# S7G7_footprint_simplified_w_ethernet_v1p.net
KiCad netlist of a schematic drawn in EAGLE
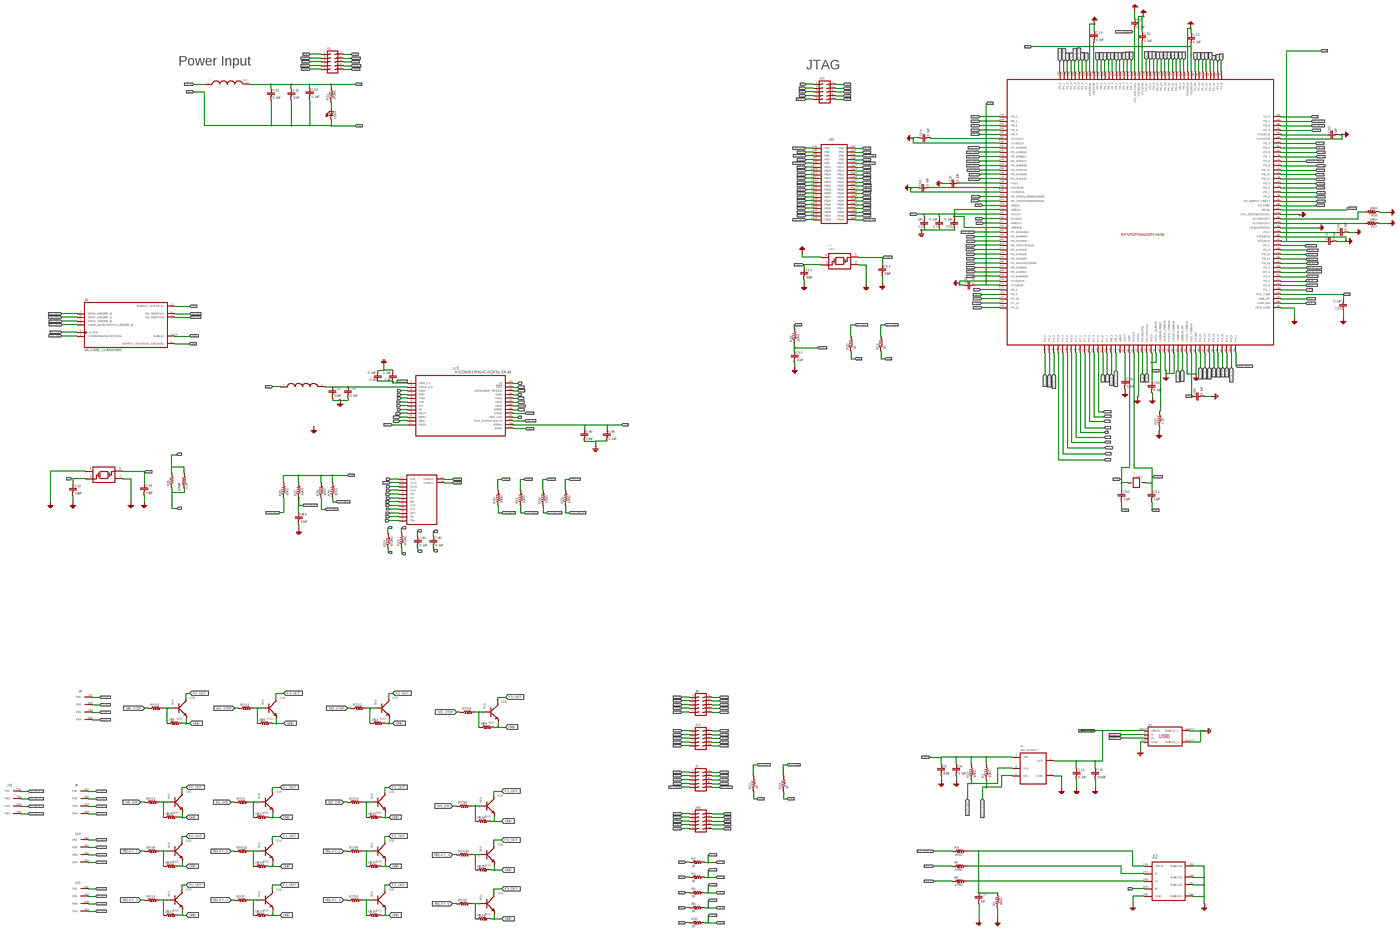
[diagram p0: schematic, sheet 1, overview]
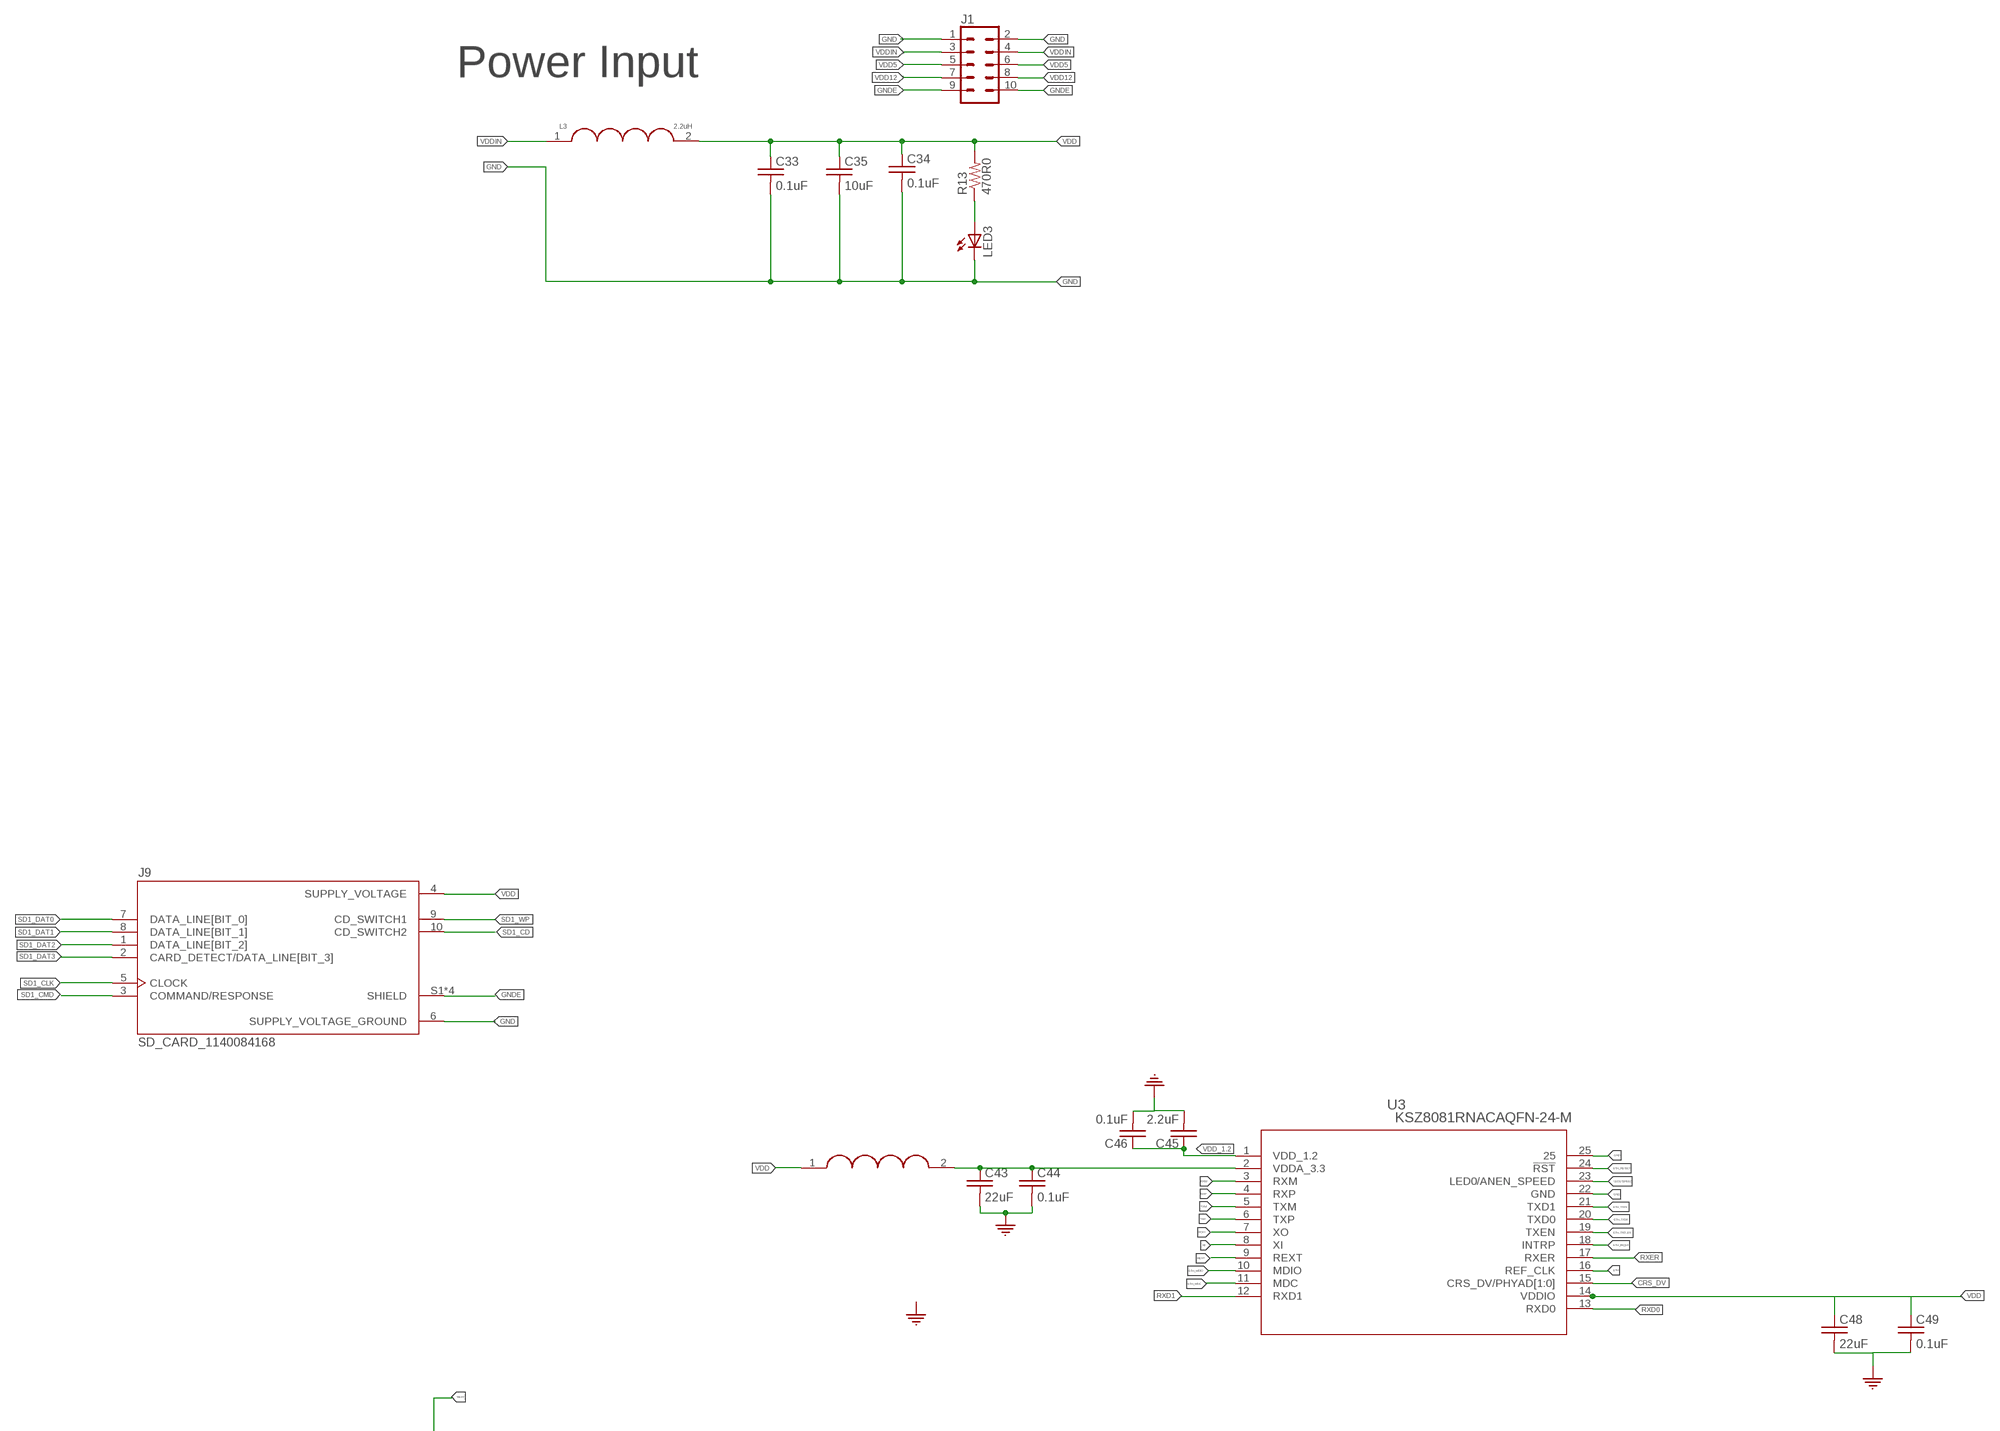
[diagram p1: schematic, sheet 1, part 1 of 4]
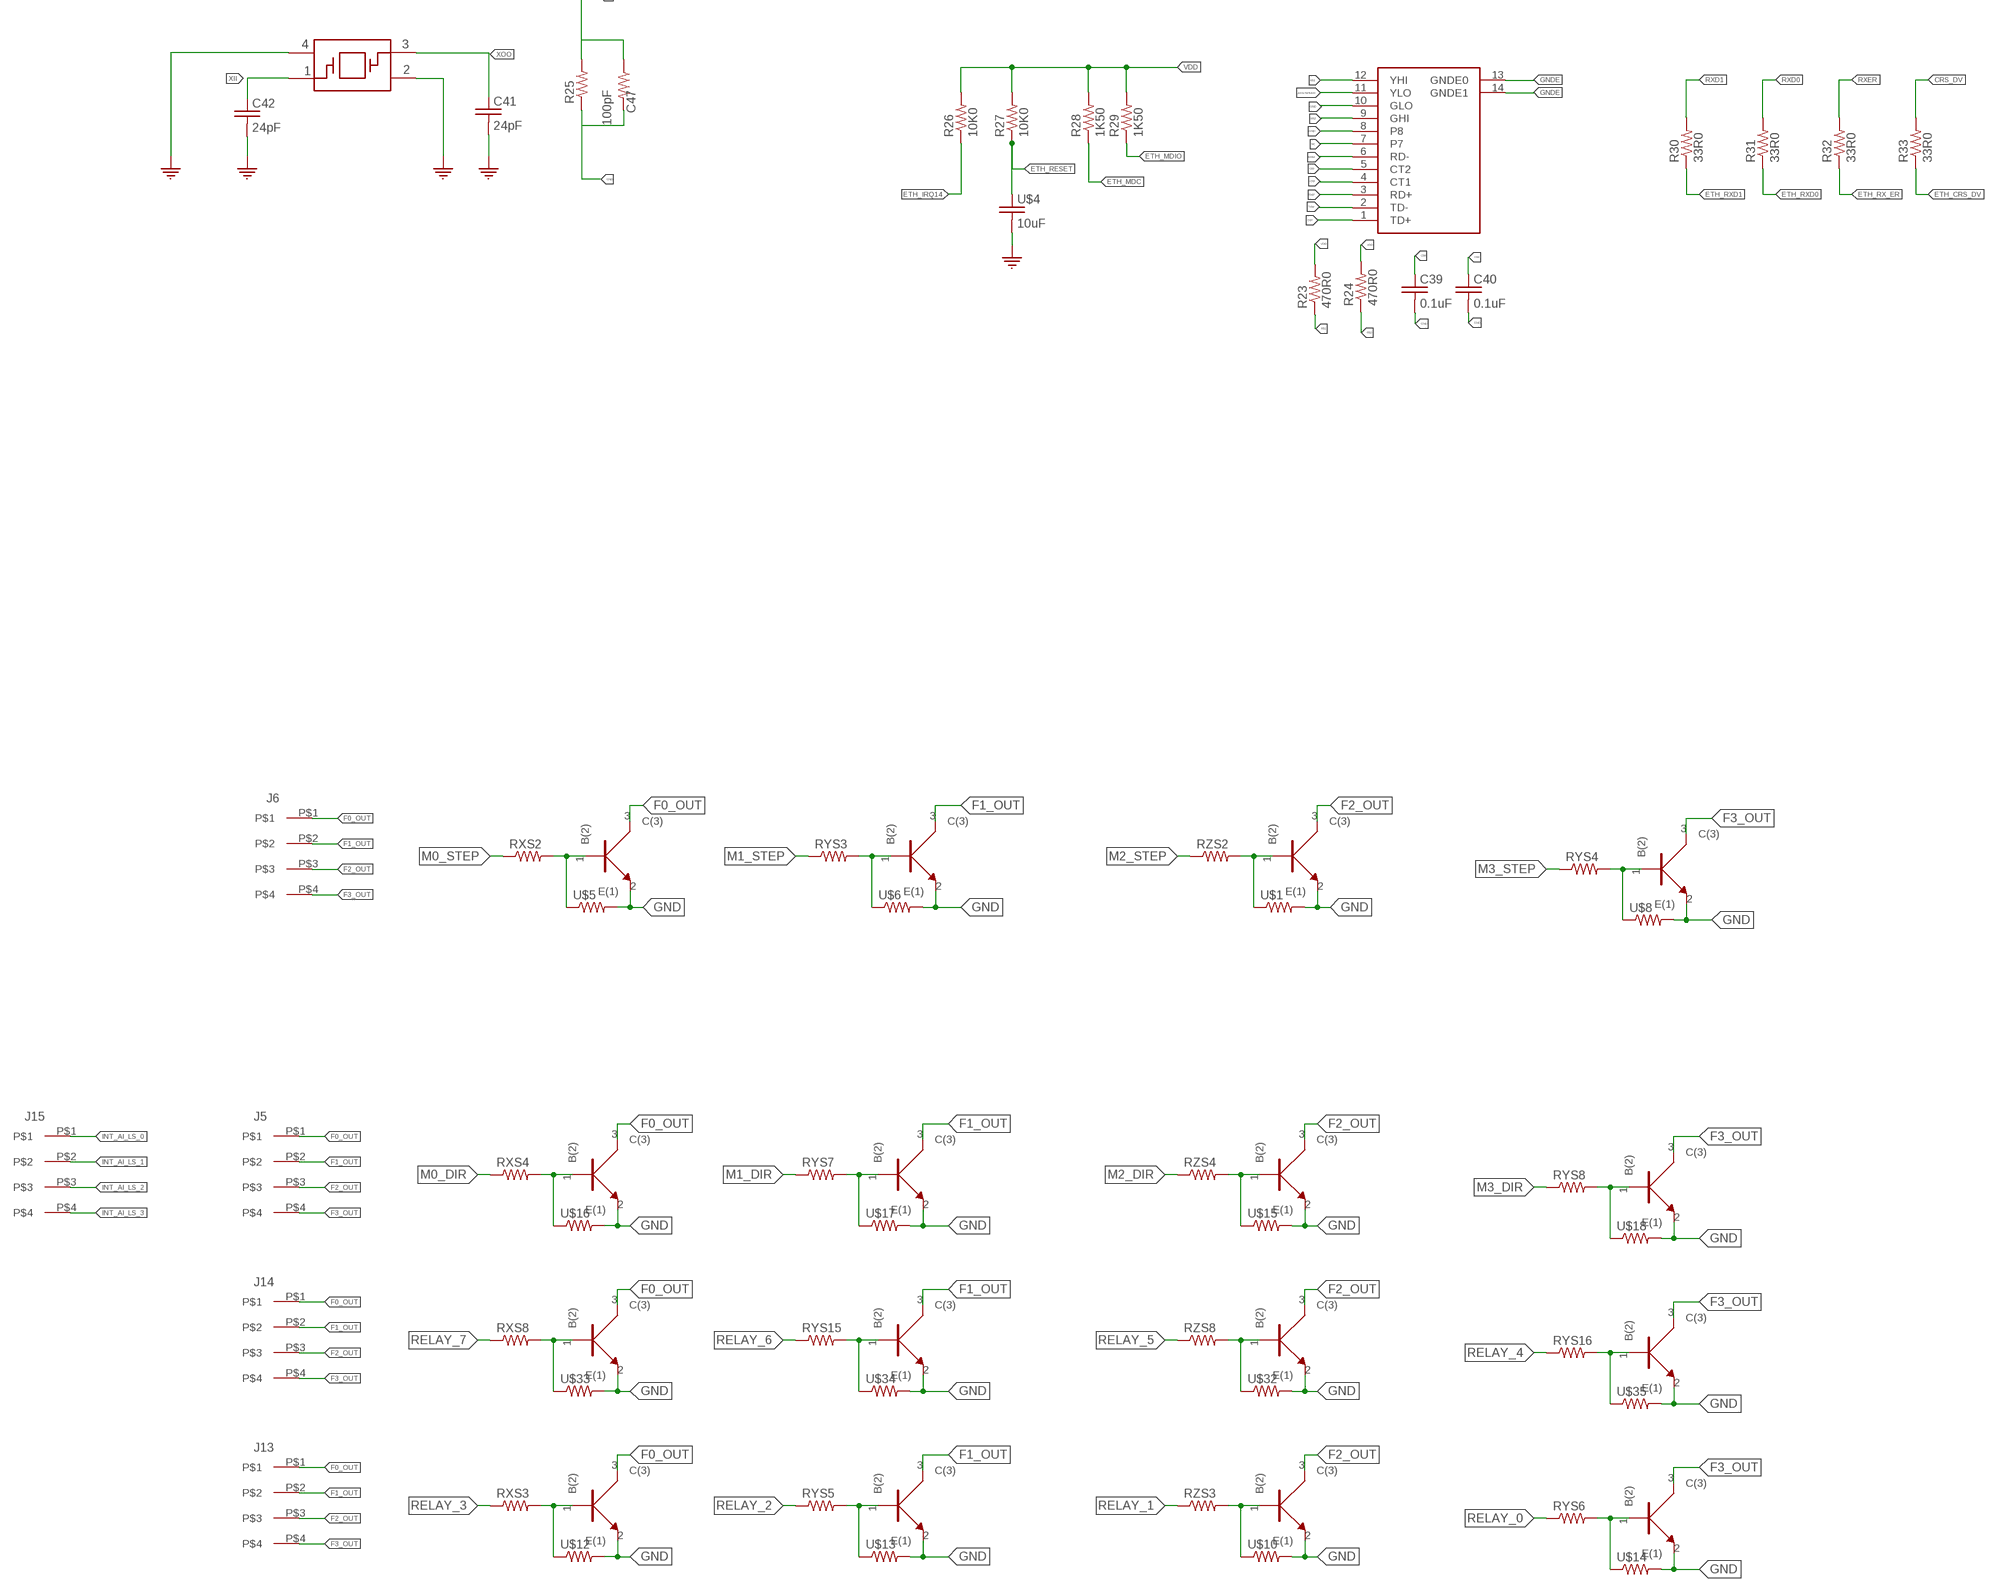
[diagram p2: schematic, sheet 1, part 2 of 4]
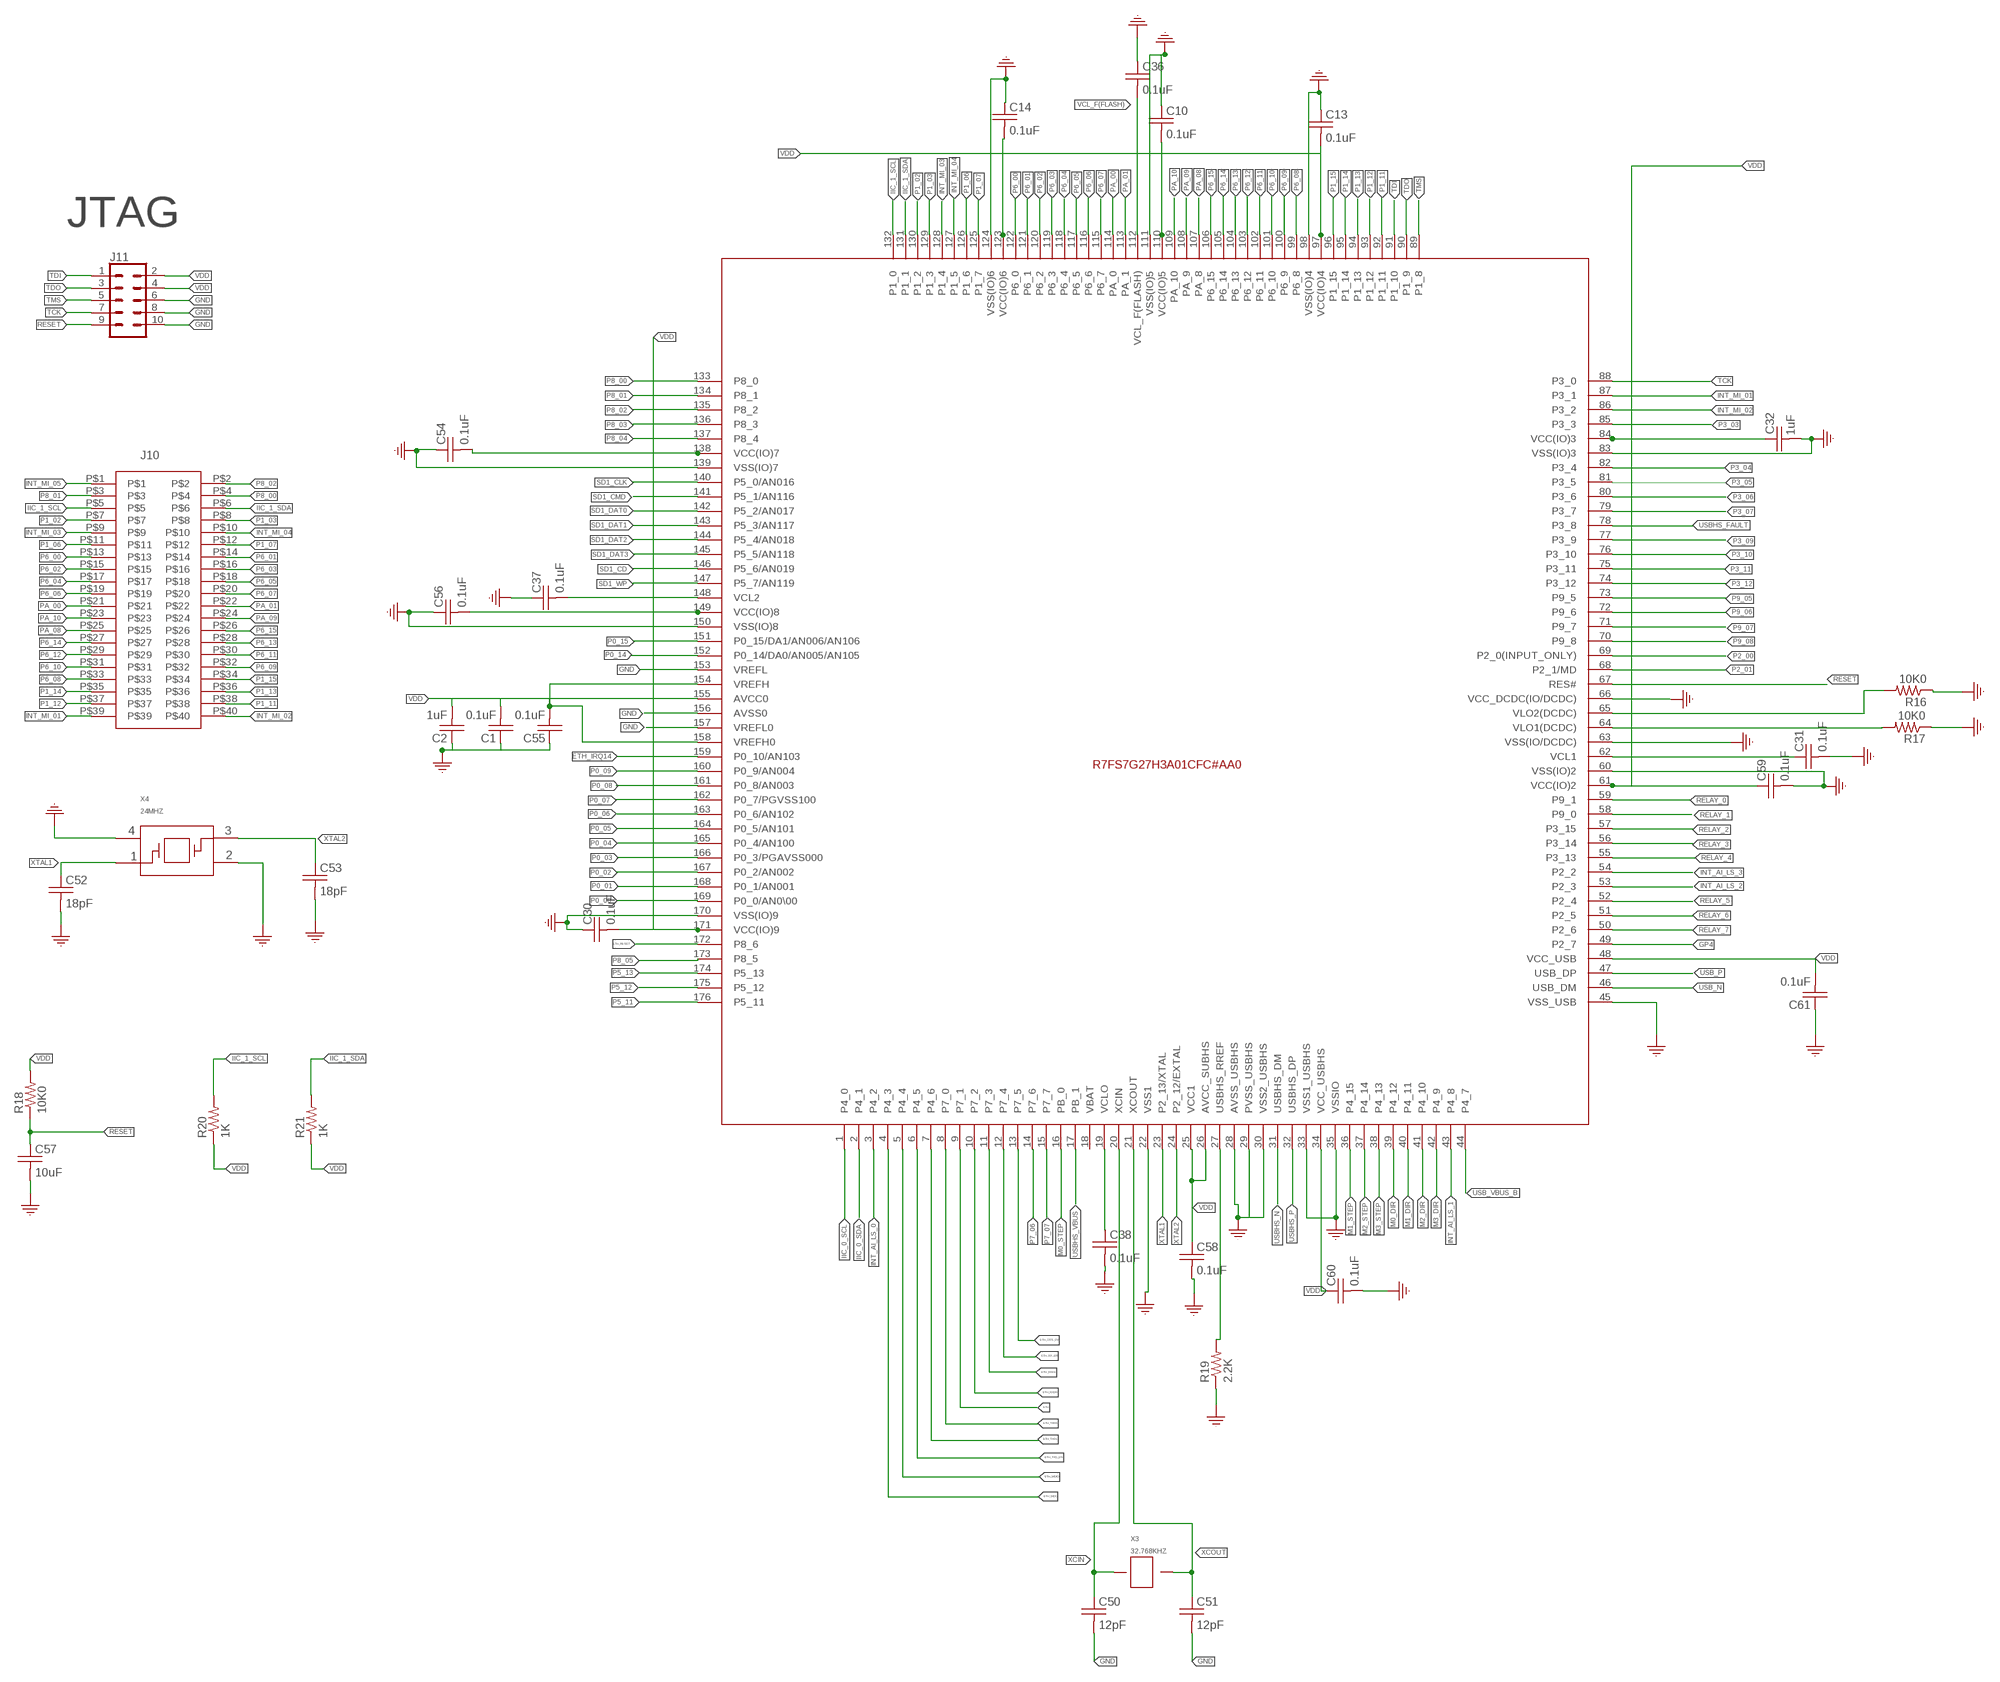
[diagram p3: schematic, sheet 1, part 3 of 4]
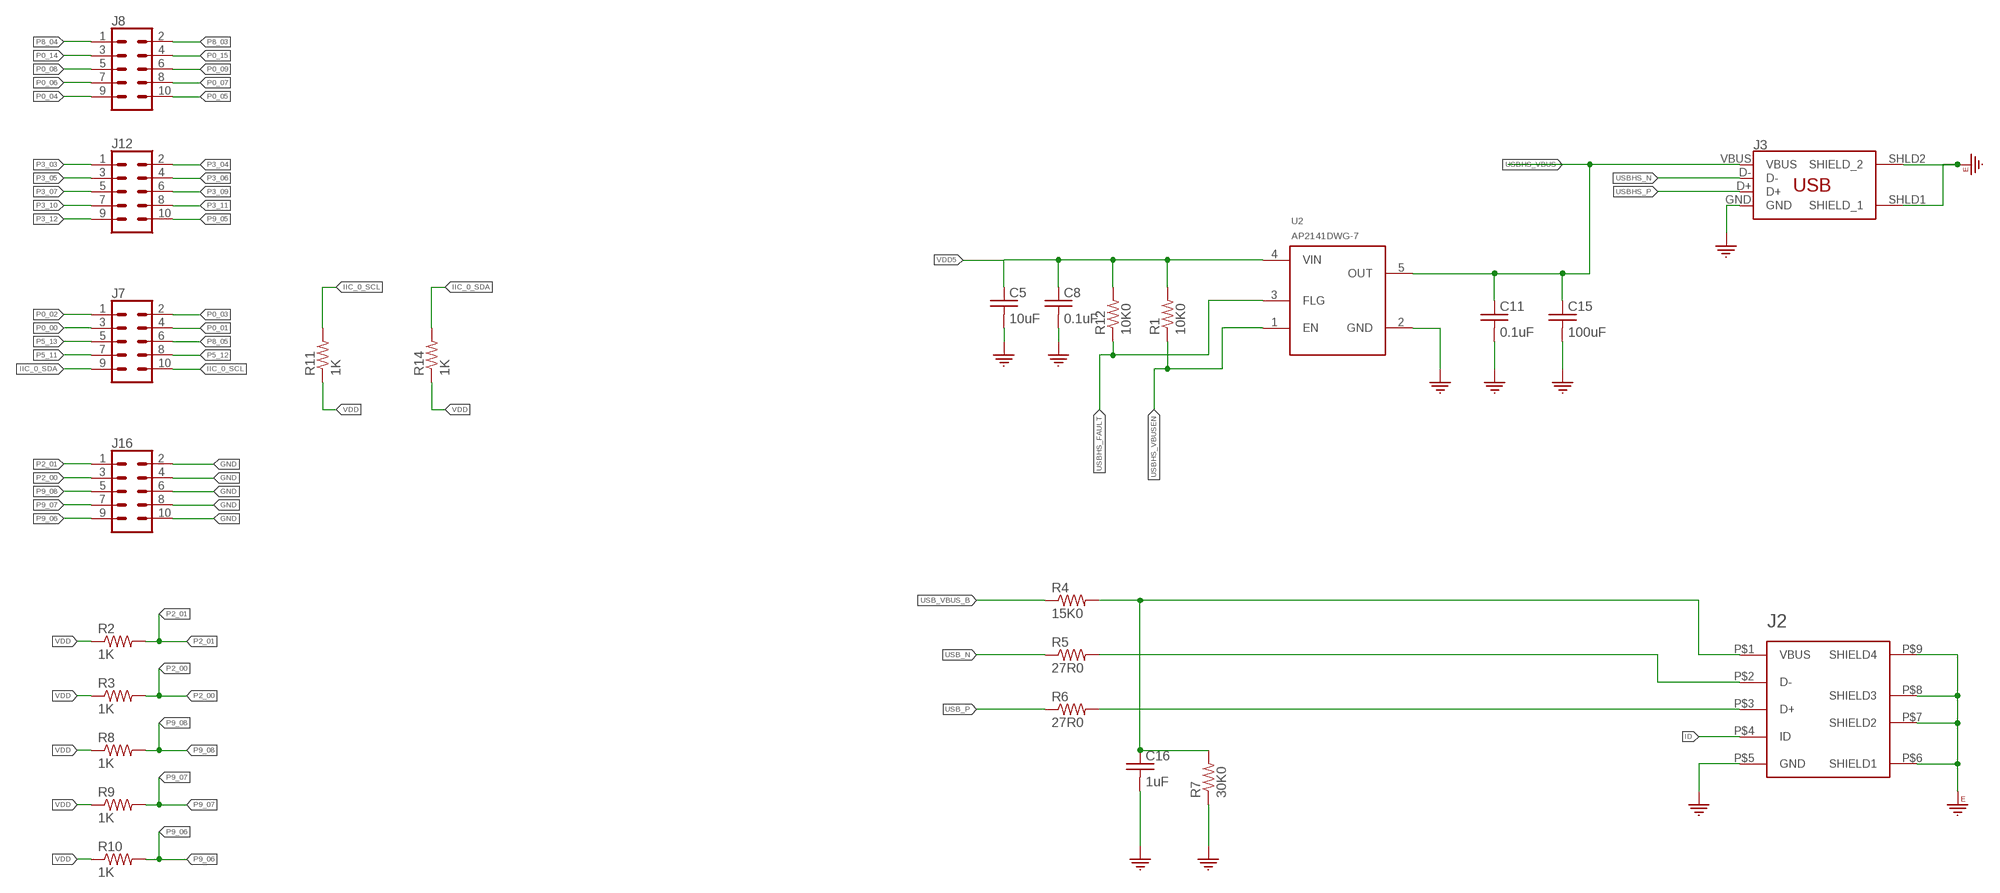
[diagram p4: schematic, sheet 1, part 4 of 4]

(export (version "E")
  (design (tool "Eeschema 10.0.6"))
  (components
    (comp (ref "C1")
      (value "0.1uF")
      (footprint "eagle-import:0402")
      (libsource (lib "eagle-import") (part "C_0402"))
    )
    (comp (ref "C2")
      (value "1uF")
      (footprint "eagle-import:0402")
      (libsource (lib "eagle-import") (part "C_0402"))
    )
    (comp (ref "C5")
      (value "10uF")
      (footprint "eagle-import:0402")
      (libsource (lib "eagle-import") (part "C_0402"))
    )
    (comp (ref "C8")
      (value "0.1uF")
      (footprint "eagle-import:0402")
      (libsource (lib "eagle-import") (part "C_0402"))
    )
    (comp (ref "C10")
      (value "0.1uF")
      (footprint "eagle-import:0402")
      (libsource (lib "eagle-import") (part "C_0402"))
    )
    (comp (ref "C11")
      (value "0.1uF")
      (footprint "eagle-import:0402")
      (libsource (lib "eagle-import") (part "C_0402"))
    )
    (comp (ref "C13")
      (value "0.1uF")
      (footprint "eagle-import:0402")
      (libsource (lib "eagle-import") (part "C_0402"))
    )
    (comp (ref "C14")
      (value "0.1uF")
      (footprint "eagle-import:0402")
      (libsource (lib "eagle-import") (part "C_0402"))
    )
    (comp (ref "C15")
      (value "100uF")
      (footprint "eagle-import:C1210")
      (libsource (lib "eagle-import") (part "C_1210"))
    )
    (comp (ref "C16")
      (value "1uF")
      (footprint "eagle-import:0402")
      (libsource (lib "eagle-import") (part "C_0402"))
    )
    (comp (ref "C30")
      (value "0.1uF")
      (footprint "eagle-import:0402")
      (libsource (lib "eagle-import") (part "C_0402"))
    )
    (comp (ref "C31")
      (value "0.1uF")
      (footprint "eagle-import:0402")
      (libsource (lib "eagle-import") (part "C_0402"))
    )
    (comp (ref "C32")
      (value "1uF")
      (footprint "eagle-import:0402")
      (libsource (lib "eagle-import") (part "C_0402"))
    )
    (comp (ref "C33")
      (value "0.1uF")
      (footprint "eagle-import:0402")
      (libsource (lib "eagle-import") (part "C_0402"))
    )
    (comp (ref "C34")
      (value "0.1uF")
      (footprint "eagle-import:0402")
      (libsource (lib "eagle-import") (part "C_0402"))
    )
    (comp (ref "C35")
      (value "10uF")
      (footprint "eagle-import:0402")
      (libsource (lib "eagle-import") (part "C_0402"))
    )
    (comp (ref "C36")
      (value "0.1uF")
      (footprint "eagle-import:0402")
      (libsource (lib "eagle-import") (part "C_0402"))
    )
    (comp (ref "C37")
      (value "0.1uF")
      (footprint "eagle-import:0402")
      (libsource (lib "eagle-import") (part "C_0402"))
    )
    (comp (ref "C38")
      (value "0.1uF")
      (footprint "eagle-import:0402")
      (libsource (lib "eagle-import") (part "C_0402"))
    )
    (comp (ref "C39")
      (value "0.1uF")
      (footprint "eagle-import:0402")
      (libsource (lib "eagle-import") (part "C_0402"))
    )
    (comp (ref "C40")
      (value "0.1uF")
      (footprint "eagle-import:0402")
      (libsource (lib "eagle-import") (part "C_0402"))
    )
    (comp (ref "C41")
      (value "24pF")
      (footprint "eagle-import:0402")
      (libsource (lib "eagle-import") (part "C_0402"))
    )
    (comp (ref "C42")
      (value "24pF")
      (footprint "eagle-import:0402")
      (libsource (lib "eagle-import") (part "C_0402"))
    )
    (comp (ref "C43")
      (value "22uF")
      (footprint "eagle-import:0603")
      (libsource (lib "eagle-import") (part "C_0603"))
    )
    (comp (ref "C44")
      (value "0.1uF")
      (footprint "eagle-import:0402")
      (libsource (lib "eagle-import") (part "C_0402"))
    )
    (comp (ref "C45")
      (value "2.2uF")
      (footprint "eagle-import:0402")
      (libsource (lib "eagle-import") (part "C_0402"))
    )
    (comp (ref "C46")
      (value "0.1uF")
      (footprint "eagle-import:0402")
      (libsource (lib "eagle-import") (part "C_0402"))
    )
    (comp (ref "C47")
      (value "100pF")
      (footprint "eagle-import:0402")
      (libsource (lib "eagle-import") (part "R_0402"))
    )
    (comp (ref "C48")
      (value "22uF")
      (footprint "eagle-import:0603")
      (libsource (lib "eagle-import") (part "C_0603"))
    )
    (comp (ref "C49")
      (value "0.1uF")
      (footprint "eagle-import:0402")
      (libsource (lib "eagle-import") (part "C_0402"))
    )
    (comp (ref "C50")
      (value "12pF")
      (footprint "eagle-import:0402")
      (libsource (lib "eagle-import") (part "C_0402"))
    )
    (comp (ref "C51")
      (value "12pF")
      (footprint "eagle-import:0402")
      (libsource (lib "eagle-import") (part "C_0402"))
    )
    (comp (ref "C52")
      (value "18pF")
      (footprint "eagle-import:0402")
      (libsource (lib "eagle-import") (part "C_0402"))
    )
    (comp (ref "C53")
      (value "18pF")
      (footprint "eagle-import:0402")
      (libsource (lib "eagle-import") (part "C_0402"))
    )
    (comp (ref "C54")
      (value "0.1uF")
      (footprint "eagle-import:0402")
      (libsource (lib "eagle-import") (part "C_0402"))
    )
    (comp (ref "C55")
      (value "0.1uF")
      (footprint "eagle-import:0402")
      (libsource (lib "eagle-import") (part "C_0402"))
    )
    (comp (ref "C56")
      (value "0.1uF")
      (footprint "eagle-import:0402")
      (libsource (lib "eagle-import") (part "C_0402"))
    )
    (comp (ref "C57")
      (value "10uF")
      (footprint "eagle-import:0402")
      (libsource (lib "eagle-import") (part "C_0402"))
    )
    (comp (ref "C58")
      (value "0.1uF")
      (footprint "eagle-import:0402")
      (libsource (lib "eagle-import") (part "C_0402"))
    )
    (comp (ref "C59")
      (value "0.1uF")
      (footprint "eagle-import:0402")
      (libsource (lib "eagle-import") (part "C_0402"))
    )
    (comp (ref "C60")
      (value "0.1uF")
      (footprint "eagle-import:0402")
      (libsource (lib "eagle-import") (part "C_0402"))
    )
    (comp (ref "C61")
      (value "0.1uF")
      (footprint "eagle-import:0402")
      (libsource (lib "eagle-import") (part "C_0402"))
    )
    (comp (ref "FB2/2")
      (value "FB_0805_120_OHM")
      (footprint "eagle-import:0805")
      (libsource (lib "eagle-import") (part "FB_0805_120_OHM"))
    )
    (comp (ref "J1")
      (value "CONN_05X2PTH")
      (footprint "eagle-import:2X5")
      (libsource (lib "eagle-import") (part "CONN_05X2PTH"))
    )
    (comp (ref "J2")
      (value "USB_MICRO-B")
      (footprint "eagle-import:USB_MICRO-B")
      (libsource (lib "eagle-import") (part "USB_MICRO-B"))
    )
    (comp (ref "J3")
      (value "USB_A")
      (footprint "eagle-import:USB_A_SMT")
      (libsource (lib "eagle-import") (part "USB_A"))
    )
    (comp (ref "J4")
      (value "RJ45_WITH_ELEC")
      (footprint "eagle-import:RJ45_TH_ELEC")
      (libsource (lib "eagle-import") (part "RJ45_WITH_ELEC"))
    )
    (comp (ref "J5")
      (value "3.81MM_1_X_4_RT_ANGLE_PLUG_HEADER")
      (footprint "eagle-import:1X4_3.81MM_PITCH")
      (libsource (lib "eagle-import") (part "3.81MM_1_X_4_RT_ANGLE_PLUG_HEADER"))
    )
    (comp (ref "J6")
      (value "3.81MM_1_X_4_RT_ANGLE_PLUG_HEADER")
      (footprint "eagle-import:1X4_3.81MM_PITCH")
      (libsource (lib "eagle-import") (part "3.81MM_1_X_4_RT_ANGLE_PLUG_HEADER"))
    )
    (comp (ref "J7")
      (value "CONN_05X2NO_SILK")
      (footprint "eagle-import:2X5_NOSILK")
      (libsource (lib "eagle-import") (part "CONN_05X2NO_SILK"))
    )
    (comp (ref "J8")
      (value "CONN_05X2NO_SILK")
      (footprint "eagle-import:2X5_NOSILK")
      (libsource (lib "eagle-import") (part "CONN_05X2NO_SILK"))
    )
    (comp (ref "J9")
      (value "SD_CARD_1140084168")
      (footprint "eagle-import:AMPHENOL_1140084168")
      (fields
        (field (name "DIGI-KEY_PART_NUMBER") "114-00841-68-1-ND")
        (field (name "MF") "Amphenol ICC")
        (field (name "MP") "114-00841-68")
      )
      (libsource (lib "eagle-import") (part "SD_CARD_1140084168"))
    )
    (comp (ref "J10")
      (value "HEADER_2_X_20_GENERIC")
      (footprint "eagle-import:HEADER_2_X_20_.1_INCH")
      (libsource (lib "eagle-import") (part "HEADER_2_X_20_GENERIC"))
    )
    (comp (ref "J11")
      (value "CONN_05X2PTH")
      (footprint "eagle-import:2X5")
      (libsource (lib "eagle-import") (part "CONN_05X2PTH"))
    )
    (comp (ref "J12")
      (value "CONN_05X2NO_SILK")
      (footprint "eagle-import:2X5_NOSILK")
      (libsource (lib "eagle-import") (part "CONN_05X2NO_SILK"))
    )
    (comp (ref "J13")
      (value "3.81MM_1_X_4_RT_ANGLE_PLUG_HEADER")
      (footprint "eagle-import:1X4_3.81MM_PITCH")
      (libsource (lib "eagle-import") (part "3.81MM_1_X_4_RT_ANGLE_PLUG_HEADER"))
    )
    (comp (ref "J14")
      (value "3.81MM_1_X_4_RT_ANGLE_PLUG_HEADER")
      (footprint "eagle-import:1X4_3.81MM_PITCH")
      (libsource (lib "eagle-import") (part "3.81MM_1_X_4_RT_ANGLE_PLUG_HEADER"))
    )
    (comp (ref "J15")
      (value "3.81MM_1_X_4_RT_ANGLE_PLUG_HEADER")
      (footprint "eagle-import:1X4_3.81MM_PITCH")
      (libsource (lib "eagle-import") (part "3.81MM_1_X_4_RT_ANGLE_PLUG_HEADER"))
    )
    (comp (ref "J16")
      (value "CONN_05X2SHD_SMD")
      (footprint "eagle-import:2X5-SHROUDED_SMD")
      (libsource (lib "eagle-import") (part "CONN_05X2SHD_SMD"))
    )
    (comp (ref "L3")
      (value "2.2uH")
      (footprint "eagle-import:1008_(2520_METRIC)")
      (libsource (lib "eagle-import") (part "INDUCTOR_1008_2.2_MH_1.3A"))
    )
    (comp (ref "LED3")
      (value "LED_0805_GREEN")
      (footprint "eagle-import:LED_0805_GREEN")
      (libsource (lib "eagle-import") (part "LED_0805_GREEN"))
    )
    (comp (ref "R1")
      (value "10K0")
      (footprint "eagle-import:0402")
      (libsource (lib "eagle-import") (part "R_0402"))
    )
    (comp (ref "R2")
      (value "1K")
      (footprint "eagle-import:0402")
      (libsource (lib "eagle-import") (part "R_0402"))
    )
    (comp (ref "R3")
      (value "1K")
      (footprint "eagle-import:0402")
      (libsource (lib "eagle-import") (part "R_0402"))
    )
    (comp (ref "R4")
      (value "15K0")
      (footprint "eagle-import:0402")
      (libsource (lib "eagle-import") (part "R_0402"))
    )
    (comp (ref "R5")
      (value "27R0")
      (footprint "eagle-import:0402")
      (libsource (lib "eagle-import") (part "R_0402"))
    )
    (comp (ref "R6")
      (value "27R0")
      (footprint "eagle-import:0402")
      (libsource (lib "eagle-import") (part "R_0402"))
    )
    (comp (ref "R7")
      (value "30K0")
      (footprint "eagle-import:0402")
      (libsource (lib "eagle-import") (part "R_0402"))
    )
    (comp (ref "R8")
      (value "1K")
      (footprint "eagle-import:0402")
      (libsource (lib "eagle-import") (part "R_0402"))
    )
    (comp (ref "R9")
      (value "1K")
      (footprint "eagle-import:0402")
      (libsource (lib "eagle-import") (part "R_0402"))
    )
    (comp (ref "R10")
      (value "1K")
      (footprint "eagle-import:0402")
      (libsource (lib "eagle-import") (part "R_0402"))
    )
    (comp (ref "R11")
      (value "1K")
      (footprint "eagle-import:0402")
      (libsource (lib "eagle-import") (part "R_0402"))
    )
    (comp (ref "R12")
      (value "10K0")
      (footprint "eagle-import:0402")
      (libsource (lib "eagle-import") (part "R_0402"))
    )
    (comp (ref "R13")
      (value "470R0")
      (footprint "eagle-import:0402")
      (libsource (lib "eagle-import") (part "R_0402"))
    )
    (comp (ref "R14")
      (value "1K")
      (footprint "eagle-import:0402")
      (libsource (lib "eagle-import") (part "R_0402"))
    )
    (comp (ref "R16")
      (value "10K0")
      (footprint "eagle-import:0402")
      (libsource (lib "eagle-import") (part "R_0402"))
    )
    (comp (ref "R17")
      (value "10K0")
      (footprint "eagle-import:0402")
      (libsource (lib "eagle-import") (part "R_0402"))
    )
    (comp (ref "R18")
      (value "10K0")
      (footprint "eagle-import:0402")
      (libsource (lib "eagle-import") (part "R_0402"))
    )
    (comp (ref "R19")
      (value "2.2K")
      (footprint "eagle-import:0402")
      (libsource (lib "eagle-import") (part "R_0402"))
    )
    (comp (ref "R20")
      (value "1K")
      (footprint "eagle-import:0402")
      (libsource (lib "eagle-import") (part "R_0402"))
    )
    (comp (ref "R21")
      (value "1K")
      (footprint "eagle-import:0402")
      (libsource (lib "eagle-import") (part "R_0402"))
    )
    (comp (ref "R23")
      (value "470R0")
      (footprint "eagle-import:0402")
      (libsource (lib "eagle-import") (part "R_0402"))
    )
    (comp (ref "R24")
      (value "470R0")
      (footprint "eagle-import:0402")
      (libsource (lib "eagle-import") (part "R_0402"))
    )
    (comp (ref "R25")
      (value "6k49")
      (footprint "eagle-import:0402")
      (libsource (lib "eagle-import") (part "R_0402"))
    )
    (comp (ref "R26")
      (value "10K0")
      (footprint "eagle-import:0402")
      (libsource (lib "eagle-import") (part "R_0402"))
    )
    (comp (ref "R27")
      (value "10K0")
      (footprint "eagle-import:0402")
      (libsource (lib "eagle-import") (part "R_0402"))
    )
    (comp (ref "R28")
      (value "1K50")
      (footprint "eagle-import:0402")
      (libsource (lib "eagle-import") (part "R_0402"))
    )
    (comp (ref "R29")
      (value "1K50")
      (footprint "eagle-import:0402")
      (libsource (lib "eagle-import") (part "R_0402"))
    )
    (comp (ref "R30")
      (value "33R0")
      (footprint "eagle-import:0402")
      (libsource (lib "eagle-import") (part "R_0402"))
    )
    (comp (ref "R31")
      (value "33R0")
      (footprint "eagle-import:0402")
      (libsource (lib "eagle-import") (part "R_0402"))
    )
    (comp (ref "R32")
      (value "33R0")
      (footprint "eagle-import:0402")
      (libsource (lib "eagle-import") (part "R_0402"))
    )
    (comp (ref "R33")
      (value "33R0")
      (footprint "eagle-import:0402")
      (libsource (lib "eagle-import") (part "R_0402"))
    )
    (comp (ref "RXS2")
      (value "1K")
      (footprint "eagle-import:0402")
      (libsource (lib "eagle-import") (part "R_0402"))
    )
    (comp (ref "RXS3")
      (value "1K")
      (footprint "eagle-import:0402")
      (libsource (lib "eagle-import") (part "R_0402"))
    )
    (comp (ref "RXS4")
      (value "1K")
      (footprint "eagle-import:0402")
      (libsource (lib "eagle-import") (part "R_0402"))
    )
    (comp (ref "RXS8")
      (value "1K")
      (footprint "eagle-import:0402")
      (libsource (lib "eagle-import") (part "R_0402"))
    )
    (comp (ref "RYS3")
      (value "1K")
      (footprint "eagle-import:0402")
      (libsource (lib "eagle-import") (part "R_0402"))
    )
    (comp (ref "RYS4")
      (value "1K")
      (footprint "eagle-import:0402")
      (libsource (lib "eagle-import") (part "R_0402"))
    )
    (comp (ref "RYS5")
      (value "1K")
      (footprint "eagle-import:0402")
      (libsource (lib "eagle-import") (part "R_0402"))
    )
    (comp (ref "RYS6")
      (value "1K")
      (footprint "eagle-import:0402")
      (libsource (lib "eagle-import") (part "R_0402"))
    )
    (comp (ref "RYS7")
      (value "1K")
      (footprint "eagle-import:0402")
      (libsource (lib "eagle-import") (part "R_0402"))
    )
    (comp (ref "RYS8")
      (value "1K")
      (footprint "eagle-import:0402")
      (libsource (lib "eagle-import") (part "R_0402"))
    )
    (comp (ref "RYS15")
      (value "1K")
      (footprint "eagle-import:0402")
      (libsource (lib "eagle-import") (part "R_0402"))
    )
    (comp (ref "RYS16")
      (value "1K")
      (footprint "eagle-import:0402")
      (libsource (lib "eagle-import") (part "R_0402"))
    )
    (comp (ref "RZS2")
      (value "1K")
      (footprint "eagle-import:0402")
      (libsource (lib "eagle-import") (part "R_0402"))
    )
    (comp (ref "RZS3")
      (value "1K")
      (footprint "eagle-import:0402")
      (libsource (lib "eagle-import") (part "R_0402"))
    )
    (comp (ref "RZS4")
      (value "1K")
      (footprint "eagle-import:0402")
      (libsource (lib "eagle-import") (part "R_0402"))
    )
    (comp (ref "RZS8")
      (value "1K")
      (footprint "eagle-import:0402")
      (libsource (lib "eagle-import") (part "R_0402"))
    )
    (comp (ref "U$1")
      (value "1K")
      (footprint "eagle-import:0402")
      (libsource (lib "eagle-import") (part "R_0402"))
    )
    (comp (ref "U$3")
      (value "XTAL_25_MHZ")
      (footprint "eagle-import:SMD_3225")
      (libsource (lib "eagle-import") (part "XTAL_25_MHZ"))
    )
    (comp (ref "U$4")
      (value "10uF")
      (footprint "eagle-import:0402")
      (libsource (lib "eagle-import") (part "C_0402"))
    )
    (comp (ref "U$5")
      (value "1K")
      (footprint "eagle-import:0402")
      (libsource (lib "eagle-import") (part "R_0402"))
    )
    (comp (ref "U$6")
      (value "1K")
      (footprint "eagle-import:0402")
      (libsource (lib "eagle-import") (part "R_0402"))
    )
    (comp (ref "U$8")
      (value "1K")
      (footprint "eagle-import:0402")
      (libsource (lib "eagle-import") (part "R_0402"))
    )
    (comp (ref "U$10")
      (value "1K")
      (footprint "eagle-import:0402")
      (libsource (lib "eagle-import") (part "R_0402"))
    )
    (comp (ref "U$12")
      (value "1K")
      (footprint "eagle-import:0402")
      (libsource (lib "eagle-import") (part "R_0402"))
    )
    (comp (ref "U$13")
      (value "1K")
      (footprint "eagle-import:0402")
      (libsource (lib "eagle-import") (part "R_0402"))
    )
    (comp (ref "U$14")
      (value "1K")
      (footprint "eagle-import:0402")
      (libsource (lib "eagle-import") (part "R_0402"))
    )
    (comp (ref "U$15")
      (value "1K")
      (footprint "eagle-import:0402")
      (libsource (lib "eagle-import") (part "R_0402"))
    )
    (comp (ref "U$16")
      (value "1K")
      (footprint "eagle-import:0402")
      (libsource (lib "eagle-import") (part "R_0402"))
    )
    (comp (ref "U$17")
      (value "1K")
      (footprint "eagle-import:0402")
      (libsource (lib "eagle-import") (part "R_0402"))
    )
    (comp (ref "U$18")
      (value "1K")
      (footprint "eagle-import:0402")
      (libsource (lib "eagle-import") (part "R_0402"))
    )
    (comp (ref "U$32")
      (value "1K")
      (footprint "eagle-import:0402")
      (libsource (lib "eagle-import") (part "R_0402"))
    )
    (comp (ref "U$33")
      (value "1K")
      (footprint "eagle-import:0402")
      (libsource (lib "eagle-import") (part "R_0402"))
    )
    (comp (ref "U$34")
      (value "1K")
      (footprint "eagle-import:0402")
      (libsource (lib "eagle-import") (part "R_0402"))
    )
    (comp (ref "U$35")
      (value "1K")
      (footprint "eagle-import:0402")
      (libsource (lib "eagle-import") (part "R_0402"))
    )
    (comp (ref "U2")
      (value "AP2141DWG-5")
      (footprint "eagle-import:SOT-23-5")
      (libsource (lib "eagle-import") (part "AP2141DWG-5"))
    )
    (comp (ref "U3")
      (value "KSZ8081RNACAQFN-24-M")
      (footprint "eagle-import:QFN-24-M")
      (fields (field (name "MANUFACTURER_PART_NUMBER") "KSZ8081RNACA"))
      (libsource (lib "eagle-import") (part "KSZ8081RNACAQFN-24-M"))
    )
    (comp (ref "U4")
      (value "S7G2LQFP176")
      (footprint "eagle-import:LQFP176_24X24")
      (fields (field (name "PARTNO") "R7FS7G27H3A01CFC#AA0"))
      (libsource (lib "eagle-import") (part "RENESAS_S7G2_X_176"))
    )
    (comp (ref "U7")
      (value "BC846BW")
      (footprint "eagle-import:SOT323")
      (libsource (lib "eagle-import") (part "BC846BW"))
    )
    (comp (ref "U8")
      (value "BC846BW")
      (footprint "eagle-import:SOT323")
      (libsource (lib "eagle-import") (part "BC846BW"))
    )
    (comp (ref "U9")
      (value "BC846BW")
      (footprint "eagle-import:SOT323")
      (libsource (lib "eagle-import") (part "BC846BW"))
    )
    (comp (ref "U10")
      (value "BC846BW")
      (footprint "eagle-import:SOT323")
      (libsource (lib "eagle-import") (part "BC846BW"))
    )
    (comp (ref "U12")
      (value "BC846BW")
      (footprint "eagle-import:SOT323")
      (libsource (lib "eagle-import") (part "BC846BW"))
    )
    (comp (ref "U13")
      (value "BC846BW")
      (footprint "eagle-import:SOT323")
      (libsource (lib "eagle-import") (part "BC846BW"))
    )
    (comp (ref "U14")
      (value "BC846BW")
      (footprint "eagle-import:SOT323")
      (libsource (lib "eagle-import") (part "BC846BW"))
    )
    (comp (ref "U15")
      (value "BC846BW")
      (footprint "eagle-import:SOT323")
      (libsource (lib "eagle-import") (part "BC846BW"))
    )
    (comp (ref "U16")
      (value "BC846BW")
      (footprint "eagle-import:SOT323")
      (libsource (lib "eagle-import") (part "BC846BW"))
    )
    (comp (ref "U17")
      (value "BC846BW")
      (footprint "eagle-import:SOT323")
      (libsource (lib "eagle-import") (part "BC846BW"))
    )
    (comp (ref "U18")
      (value "BC846BW")
      (footprint "eagle-import:SOT323")
      (libsource (lib "eagle-import") (part "BC846BW"))
    )
    (comp (ref "U19")
      (value "BC846BW")
      (footprint "eagle-import:SOT323")
      (libsource (lib "eagle-import") (part "BC846BW"))
    )
    (comp (ref "U32")
      (value "BC846BW")
      (footprint "eagle-import:SOT323")
      (libsource (lib "eagle-import") (part "BC846BW"))
    )
    (comp (ref "U33")
      (value "BC846BW")
      (footprint "eagle-import:SOT323")
      (libsource (lib "eagle-import") (part "BC846BW"))
    )
    (comp (ref "U34")
      (value "BC846BW")
      (footprint "eagle-import:SOT323")
      (libsource (lib "eagle-import") (part "BC846BW"))
    )
    (comp (ref "U35")
      (value "BC846BW")
      (footprint "eagle-import:SOT323")
      (libsource (lib "eagle-import") (part "BC846BW"))
    )
    (comp (ref "X3")
      (value "32.768KHZ")
      (footprint "eagle-import:SMD_X_2_PADS")
      (libsource (lib "eagle-import") (part "XTAL_32.768KHZ"))
    )
    (comp (ref "X4")
      (value "24MHZ")
      (footprint "eagle-import:SMD_3225")
      (libsource (lib "eagle-import") (part "XTAL_24_MHZ"))
    )
  )
  (nets
    (net (code "1") (name "C58") (class "Default")
      (node (ref "C39") (pin "P$1") (pinfunction "1_P$1") (pintype "passive"))
      (node (ref "J4") (pin "4") (pinfunction "CT1_4") (pintype "bidirectional"))
    )
    (net (code "2") (name "C60") (class "Default")
      (node (ref "C40") (pin "P$1") (pinfunction "1_P$1") (pintype "passive"))
      (node (ref "J4") (pin "5") (pinfunction "CT2_5") (pintype "bidirectional"))
    )
    (net (code "3") (name "CRS_DV") (class "Default")
      (node (ref "R33") (pin "P$2") (pinfunction "2_P$2") (pintype "passive"))
      (node (ref "U3") (pin "15") (pinfunction "CRS_DV/PHYAD[1:0]_15") (pintype "bidirectional"))
    )
    (net (code "4") (name "ETH") (class "Default")
      (node (ref "U3") (pin "16") (pinfunction "REF_CLK_16") (pintype "bidirectional"))
      (node (ref "U4") (pin "9") (pinfunction "P7_1_9") (pintype "bidirectional"))
    )
    (net (code "5") (name "ETH_CRS_DV") (class "Default")
      (node (ref "R33") (pin "P$1") (pinfunction "1_P$1") (pintype "passive"))
      (node (ref "U4") (pin "13") (pinfunction "P7_5_13") (pintype "bidirectional"))
    )
    (net (code "6") (name "ETH_IRQ14") (class "Default")
      (node (ref "R26") (pin "P$1") (pinfunction "1_P$1") (pintype "passive"))
      (node (ref "U3") (pin "18") (pinfunction "INTRP_18") (pintype "bidirectional"))
      (node (ref "U4") (pin "159") (pinfunction "P0_10/AN103_159") (pintype "bidirectional"))
    )
    (net (code "7") (name "ETH_MDC") (class "Default")
      (node (ref "R28") (pin "P$1") (pinfunction "1_P$1") (pintype "passive"))
      (node (ref "U3") (pin "11") (pinfunction "MDC_11") (pintype "input"))
      (node (ref "U4") (pin "4") (pinfunction "P4_3_4") (pintype "bidirectional"))
    )
    (net (code "8") (name "ETH_MDIO") (class "Default")
      (node (ref "R29") (pin "P$1") (pinfunction "1_P$1") (pintype "passive"))
      (node (ref "U3") (pin "10") (pinfunction "MDIO_10") (pintype "bidirectional"))
      (node (ref "U4") (pin "5") (pinfunction "P4_4_5") (pintype "bidirectional"))
    )
    (net (code "9") (name "ETH_RESET") (class "Default")
      (node (ref "R27") (pin "P$1") (pinfunction "1_P$1") (pintype "passive"))
      (node (ref "U$4") (pin "P$1") (pinfunction "1_P$1") (pintype "passive"))
      (node (ref "U3") (pin "24") (pinfunction "~{RST}_24") (pintype "input"))
      (node (ref "U4") (pin "172") (pinfunction "P8_6_172") (pintype "bidirectional"))
    )
    (net (code "10") (name "ETH_RXD0") (class "Default")
      (node (ref "R31") (pin "P$1") (pinfunction "1_P$1") (pintype "passive"))
      (node (ref "U4") (pin "10") (pinfunction "P7_2_10") (pintype "bidirectional"))
    )
    (net (code "11") (name "ETH_RXD1") (class "Default")
      (node (ref "R30") (pin "P$1") (pinfunction "1_P$1") (pintype "passive"))
      (node (ref "U4") (pin "11") (pinfunction "P7_3_11") (pintype "bidirectional"))
    )
    (net (code "12") (name "ETH_RX_ER") (class "Default")
      (node (ref "R32") (pin "P$1") (pinfunction "1_P$1") (pintype "passive"))
      (node (ref "U4") (pin "12") (pinfunction "P7_4_12") (pintype "bidirectional"))
    )
    (net (code "13") (name "ETH_TXD0") (class "Default")
      (node (ref "U3") (pin "20") (pinfunction "TXD0_20") (pintype "input"))
      (node (ref "U4") (pin "8") (pinfunction "P7_0_8") (pintype "bidirectional"))
    )
    (net (code "14") (name "ETH_TXD1") (class "Default")
      (node (ref "U3") (pin "21") (pinfunction "TXD1_21") (pintype "bidirectional"))
      (node (ref "U4") (pin "7") (pinfunction "P4_6_7") (pintype "bidirectional"))
    )
    (net (code "15") (name "ETH_TXD_EN") (class "Default")
      (node (ref "U3") (pin "19") (pinfunction "TXEN_19") (pintype "input"))
      (node (ref "U4") (pin "6") (pinfunction "P4_5_6") (pintype "bidirectional"))
    )
    (net (code "16") (name "F0_OUT") (class "Default")
      (node (ref "J13") (pin "P$1") (pinfunction "P$1_P$1") (pintype "bidirectional"))
      (node (ref "J14") (pin "P$1") (pinfunction "P$1_P$1") (pintype "bidirectional"))
      (node (ref "J5") (pin "P$1") (pinfunction "P$1_P$1") (pintype "bidirectional"))
      (node (ref "J6") (pin "P$1") (pinfunction "P$1_P$1") (pintype "bidirectional"))
      (node (ref "U13") (pin "3") (pinfunction "C(3)_3") (pintype "input"))
      (node (ref "U17") (pin "3") (pinfunction "C(3)_3") (pintype "input"))
      (node (ref "U33") (pin "3") (pinfunction "C(3)_3") (pintype "input"))
      (node (ref "U8") (pin "3") (pinfunction "C(3)_3") (pintype "input"))
    )
    (net (code "17") (name "F1_OUT") (class "Default")
      (node (ref "J13") (pin "P$2") (pinfunction "P$2_P$2") (pintype "bidirectional"))
      (node (ref "J14") (pin "P$2") (pinfunction "P$2_P$2") (pintype "bidirectional"))
      (node (ref "J5") (pin "P$2") (pinfunction "P$2_P$2") (pintype "bidirectional"))
      (node (ref "J6") (pin "P$2") (pinfunction "P$2_P$2") (pintype "bidirectional"))
      (node (ref "U14") (pin "3") (pinfunction "C(3)_3") (pintype "input"))
      (node (ref "U18") (pin "3") (pinfunction "C(3)_3") (pintype "input"))
      (node (ref "U34") (pin "3") (pinfunction "C(3)_3") (pintype "input"))
      (node (ref "U9") (pin "3") (pinfunction "C(3)_3") (pintype "input"))
    )
    (net (code "18") (name "F2_OUT") (class "Default")
      (node (ref "J13") (pin "P$3") (pinfunction "P$3_P$3") (pintype "bidirectional"))
      (node (ref "J14") (pin "P$3") (pinfunction "P$3_P$3") (pintype "bidirectional"))
      (node (ref "J5") (pin "P$3") (pinfunction "P$3_P$3") (pintype "bidirectional"))
      (node (ref "J6") (pin "P$3") (pinfunction "P$3_P$3") (pintype "bidirectional"))
      (node (ref "U12") (pin "3") (pinfunction "C(3)_3") (pintype "input"))
      (node (ref "U16") (pin "3") (pinfunction "C(3)_3") (pintype "input"))
      (node (ref "U32") (pin "3") (pinfunction "C(3)_3") (pintype "input"))
      (node (ref "U7") (pin "3") (pinfunction "C(3)_3") (pintype "input"))
    )
    (net (code "19") (name "F3_OUT") (class "Default")
      (node (ref "J13") (pin "P$4") (pinfunction "P$4_P$4") (pintype "bidirectional"))
      (node (ref "J14") (pin "P$4") (pinfunction "P$4_P$4") (pintype "bidirectional"))
      (node (ref "J5") (pin "P$4") (pinfunction "P$4_P$4") (pintype "bidirectional"))
      (node (ref "J6") (pin "P$4") (pinfunction "P$4_P$4") (pintype "bidirectional"))
      (node (ref "U10") (pin "3") (pinfunction "C(3)_3") (pintype "input"))
      (node (ref "U15") (pin "3") (pinfunction "C(3)_3") (pintype "input"))
      (node (ref "U19") (pin "3") (pinfunction "C(3)_3") (pintype "input"))
      (node (ref "U35") (pin "3") (pinfunction "C(3)_3") (pintype "input"))
    )
    (net (code "20") (name "GND") (class "Default")
      (node (ref "C1") (pin "P$1") (pinfunction "1_P$1") (pintype "passive"))
      (node (ref "C10") (pin "P$1") (pinfunction "1_P$1") (pintype "passive"))
      (node (ref "C11") (pin "P$2") (pinfunction "2_P$2") (pintype "passive"))
      (node (ref "C13") (pin "P$1") (pinfunction "1_P$1") (pintype "passive"))
      (node (ref "C14") (pin "P$1") (pinfunction "1_P$1") (pintype "passive"))
      (node (ref "C15") (pin "2") (pinfunction "2_2") (pintype "passive"))
      (node (ref "C16") (pin "P$2") (pinfunction "2_P$2") (pintype "passive"))
      (node (ref "C2") (pin "P$1") (pinfunction "1_P$1") (pintype "passive"))
      (node (ref "C30") (pin "P$1") (pinfunction "1_P$1") (pintype "passive"))
      (node (ref "C31") (pin "P$2") (pinfunction "2_P$2") (pintype "passive"))
      (node (ref "C32") (pin "P$2") (pinfunction "2_P$2") (pintype "passive"))
      (node (ref "C33") (pin "P$2") (pinfunction "2_P$2") (pintype "passive"))
      (node (ref "C34") (pin "P$2") (pinfunction "2_P$2") (pintype "passive"))
      (node (ref "C35") (pin "P$2") (pinfunction "2_P$2") (pintype "passive"))
      (node (ref "C36") (pin "P$1") (pinfunction "1_P$1") (pintype "passive"))
      (node (ref "C37") (pin "P$1") (pinfunction "1_P$1") (pintype "passive"))
      (node (ref "C38") (pin "P$2") (pinfunction "2_P$2") (pintype "passive"))
      (node (ref "C39") (pin "P$2") (pinfunction "2_P$2") (pintype "passive"))
      (node (ref "C40") (pin "P$2") (pinfunction "2_P$2") (pintype "passive"))
      (node (ref "C41") (pin "P$2") (pinfunction "2_P$2") (pintype "passive"))
      (node (ref "C42") (pin "P$2") (pinfunction "2_P$2") (pintype "passive"))
      (node (ref "C43") (pin "2") (pinfunction "2_2") (pintype "passive"))
      (node (ref "C44") (pin "P$2") (pinfunction "2_P$2") (pintype "passive"))
      (node (ref "C45") (pin "P$2") (pinfunction "2_P$2") (pintype "passive"))
      (node (ref "C46") (pin "P$2") (pinfunction "2_P$2") (pintype "passive"))
      (node (ref "C47") (pin "P$2") (pinfunction "2_P$2") (pintype "passive"))
      (node (ref "C48") (pin "2") (pinfunction "2_2") (pintype "passive"))
      (node (ref "C49") (pin "P$2") (pinfunction "2_P$2") (pintype "passive"))
      (node (ref "C5") (pin "P$2") (pinfunction "2_P$2") (pintype "passive"))
      (node (ref "C50") (pin "P$2") (pinfunction "2_P$2") (pintype "passive"))
      (node (ref "C51") (pin "P$2") (pinfunction "2_P$2") (pintype "passive"))
      (node (ref "C52") (pin "P$2") (pinfunction "2_P$2") (pintype "passive"))
      (node (ref "C53") (pin "P$2") (pinfunction "2_P$2") (pintype "passive"))
      (node (ref "C54") (pin "P$1") (pinfunction "1_P$1") (pintype "passive"))
      (node (ref "C55") (pin "P$1") (pinfunction "1_P$1") (pintype "passive"))
      (node (ref "C56") (pin "P$1") (pinfunction "1_P$1") (pintype "passive"))
      (node (ref "C57") (pin "P$2") (pinfunction "2_P$2") (pintype "passive"))
      (node (ref "C58") (pin "P$2") (pinfunction "2_P$2") (pintype "passive"))
      (node (ref "C59") (pin "P$2") (pinfunction "2_P$2") (pintype "passive"))
      (node (ref "C60") (pin "P$2") (pinfunction "2_P$2") (pintype "passive"))
      (node (ref "C61") (pin "P$1") (pinfunction "1_P$1") (pintype "passive"))
      (node (ref "C8") (pin "P$2") (pinfunction "2_P$2") (pintype "passive"))
      (node (ref "J1") (pin "1") (pinfunction "1_1") (pintype "passive"))
      (node (ref "J1") (pin "2") (pinfunction "2_2") (pintype "passive"))
      (node (ref "J11") (pin "10") (pinfunction "10_10") (pintype "passive"))
      (node (ref "J11") (pin "6") (pinfunction "6_6") (pintype "passive"))
      (node (ref "J11") (pin "8") (pinfunction "8_8") (pintype "passive"))
      (node (ref "J16") (pin "10") (pinfunction "10_10") (pintype "passive"))
      (node (ref "J16") (pin "2") (pinfunction "2_2") (pintype "passive"))
      (node (ref "J16") (pin "4") (pinfunction "4_4") (pintype "passive"))
      (node (ref "J16") (pin "6") (pinfunction "6_6") (pintype "passive"))
      (node (ref "J16") (pin "8") (pinfunction "8_8") (pintype "passive"))
      (node (ref "J2") (pin "P$5") (pinfunction "GND_P$5") (pintype "bidirectional"))
      (node (ref "J3") (pin "GND") (pinfunction "GND_GND") (pintype "power_in"))
      (node (ref "J4") (pin "10") (pinfunction "GLO_10") (pintype "bidirectional"))
      (node (ref "J4") (pin "8") (pinfunction "P8_8") (pintype "bidirectional"))
      (node (ref "J9") (pin "6") (pinfunction "SUPPLY_VOLTAGE_GROUND_6") (pintype "power_in"))
      (node (ref "LED3") (pin "C") (pinfunction "C_C") (pintype "passive"))
      (node (ref "R16") (pin "P$1") (pinfunction "1_P$1") (pintype "passive"))
      (node (ref "R17") (pin "P$1") (pinfunction "1_P$1") (pintype "passive"))
      (node (ref "R19") (pin "P$1") (pinfunction "1_P$1") (pintype "passive"))
      (node (ref "R25") (pin "P$1") (pinfunction "1_P$1") (pintype "passive"))
      (node (ref "R7") (pin "P$1") (pinfunction "1_P$1") (pintype "passive"))
      (node (ref "U$1") (pin "P$2") (pinfunction "2_P$2") (pintype "passive"))
      (node (ref "U$10") (pin "P$2") (pinfunction "2_P$2") (pintype "passive"))
      (node (ref "U$12") (pin "P$2") (pinfunction "2_P$2") (pintype "passive"))
      (node (ref "U$13") (pin "P$2") (pinfunction "2_P$2") (pintype "passive"))
      (node (ref "U$14") (pin "P$2") (pinfunction "2_P$2") (pintype "passive"))
      (node (ref "U$15") (pin "P$2") (pinfunction "2_P$2") (pintype "passive"))
      (node (ref "U$16") (pin "P$2") (pinfunction "2_P$2") (pintype "passive"))
      (node (ref "U$17") (pin "P$2") (pinfunction "2_P$2") (pintype "passive"))
      (node (ref "U$18") (pin "P$2") (pinfunction "2_P$2") (pintype "passive"))
      (node (ref "U$3") (pin "2") (pinfunction "2_2") (pintype "bidirectional"))
      (node (ref "U$3") (pin "4") (pinfunction "4_4") (pintype "bidirectional"))
      (node (ref "U$32") (pin "P$2") (pinfunction "2_P$2") (pintype "passive"))
      (node (ref "U$33") (pin "P$2") (pinfunction "2_P$2") (pintype "passive"))
      (node (ref "U$34") (pin "P$2") (pinfunction "2_P$2") (pintype "passive"))
      (node (ref "U$35") (pin "P$2") (pinfunction "2_P$2") (pintype "passive"))
      (node (ref "U$4") (pin "P$2") (pinfunction "2_P$2") (pintype "passive"))
      (node (ref "U$5") (pin "P$2") (pinfunction "2_P$2") (pintype "passive"))
      (node (ref "U$6") (pin "P$2") (pinfunction "2_P$2") (pintype "passive"))
      (node (ref "U$8") (pin "P$2") (pinfunction "2_P$2") (pintype "passive"))
      (node (ref "U10") (pin "2") (pinfunction "E(1)_2") (pintype "output"))
      (node (ref "U12") (pin "2") (pinfunction "E(1)_2") (pintype "output"))
      (node (ref "U13") (pin "2") (pinfunction "E(1)_2") (pintype "output"))
      (node (ref "U14") (pin "2") (pinfunction "E(1)_2") (pintype "output"))
      (node (ref "U15") (pin "2") (pinfunction "E(1)_2") (pintype "output"))
      (node (ref "U16") (pin "2") (pinfunction "E(1)_2") (pintype "output"))
      (node (ref "U17") (pin "2") (pinfunction "E(1)_2") (pintype "output"))
      (node (ref "U18") (pin "2") (pinfunction "E(1)_2") (pintype "output"))
      (node (ref "U19") (pin "2") (pinfunction "E(1)_2") (pintype "output"))
      (node (ref "U2") (pin "2") (pinfunction "GND_2") (pintype "input"))
      (node (ref "U3") (pin "22") (pinfunction "GND_22") (pintype "power_in"))
      (node (ref "U3") (pin "25") (pinfunction "25_25") (pintype "passive"))
      (node (ref "U32") (pin "2") (pinfunction "E(1)_2") (pintype "output"))
      (node (ref "U33") (pin "2") (pinfunction "E(1)_2") (pintype "output"))
      (node (ref "U34") (pin "2") (pinfunction "E(1)_2") (pintype "output"))
      (node (ref "U35") (pin "2") (pinfunction "E(1)_2") (pintype "output"))
      (node (ref "U4") (pin "111") (pinfunction "VSS(IO)5_111") (pintype "bidirectional"))
      (node (ref "U4") (pin "124") (pinfunction "VSS(IO)6_124") (pintype "bidirectional"))
      (node (ref "U4") (pin "139") (pinfunction "VSS(IO)7_139") (pintype "bidirectional"))
      (node (ref "U4") (pin "150") (pinfunction "VSS(IO)8_150") (pintype "bidirectional"))
      (node (ref "U4") (pin "153") (pinfunction "VREFL_153") (pintype "bidirectional"))
      (node (ref "U4") (pin "156") (pinfunction "AVSS0_156") (pintype "bidirectional"))
      (node (ref "U4") (pin "157") (pinfunction "VREFL0_157") (pintype "bidirectional"))
      (node (ref "U4") (pin "170") (pinfunction "VSS(IO)9_170") (pintype "bidirectional"))
      (node (ref "U4") (pin "22") (pinfunction "VSS1_22") (pintype "bidirectional"))
      (node (ref "U4") (pin "28") (pinfunction "AVSS_USBHS_28") (pintype "bidirectional"))
      (node (ref "U4") (pin "29") (pinfunction "PVSS_USBHS_29") (pintype "bidirectional"))
      (node (ref "U4") (pin "30") (pinfunction "VSS2_USBHS_30") (pintype "bidirectional"))
      (node (ref "U4") (pin "33") (pinfunction "VSS1_USBHS_33") (pintype "bidirectional"))
      (node (ref "U4") (pin "35") (pinfunction "VSSIO_35") (pintype "bidirectional"))
      (node (ref "U4") (pin "45") (pinfunction "VSS_USB_45") (pintype "bidirectional"))
      (node (ref "U4") (pin "60") (pinfunction "VSS(IO)2_60") (pintype "bidirectional"))
      (node (ref "U4") (pin "63") (pinfunction "VSS(IO/DCDC)_63") (pintype "bidirectional"))
      (node (ref "U4") (pin "66") (pinfunction "VCC_DCDC(IO/DCDC)_66") (pintype "bidirectional"))
      (node (ref "U4") (pin "83") (pinfunction "VSS(IO)3_83") (pintype "bidirectional"))
      (node (ref "U4") (pin "98") (pinfunction "VSS(IO)4_98") (pintype "bidirectional"))
      (node (ref "U7") (pin "2") (pinfunction "E(1)_2") (pintype "output"))
      (node (ref "U8") (pin "2") (pinfunction "E(1)_2") (pintype "output"))
      (node (ref "U9") (pin "2") (pinfunction "E(1)_2") (pintype "output"))
      (node (ref "X4") (pin "2") (pinfunction "2_2") (pintype "bidirectional"))
      (node (ref "X4") (pin "4") (pinfunction "4_4") (pintype "bidirectional"))
    )
    (net (code "21") (name "GNDE") (class "Default")
      (node (ref "J1") (pin "10") (pinfunction "10_10") (pintype "passive"))
      (node (ref "J1") (pin "9") (pinfunction "9_9") (pintype "passive"))
      (node (ref "J2") (pin "P$6") (pinfunction "SHIELD1_P$6") (pintype "bidirectional"))
      (node (ref "J2") (pin "P$7") (pinfunction "SHIELD2_P$7") (pintype "bidirectional"))
      (node (ref "J2") (pin "P$8") (pinfunction "SHIELD3_P$8") (pintype "bidirectional"))
      (node (ref "J2") (pin "P$9") (pinfunction "SHIELD4_P$9") (pintype "bidirectional"))
      (node (ref "J3") (pin "SHLD1") (pinfunction "SHIELD_1_SHLD1") (pintype "bidirectional"))
      (node (ref "J3") (pin "SHLD2") (pinfunction "SHIELD_2_SHLD2") (pintype "bidirectional"))
      (node (ref "J4") (pin "13") (pinfunction "GNDE0_13") (pintype "bidirectional"))
      (node (ref "J4") (pin "14") (pinfunction "GNDE1_14") (pintype "bidirectional"))
      (node (ref "J9") (pin "S1") (pinfunction "SHIELD_S1") (pintype "passive"))
      (node (ref "J9") (pin "S2") (pinfunction "SHIELD_S2") (pintype "passive"))
      (node (ref "J9") (pin "S3") (pinfunction "SHIELD_S3") (pintype "passive"))
      (node (ref "J9") (pin "S4") (pinfunction "SHIELD_S4") (pintype "passive"))
    )
    (net (code "22") (name "GP4") (class "Default")
      (node (ref "U4") (pin "49") (pinfunction "P2_7_49") (pintype "bidirectional"))
    )
    (net (code "23") (name "ID") (class "Default")
      (node (ref "J2") (pin "P$4") (pinfunction "ID_P$4") (pintype "bidirectional"))
    )
    (net (code "24") (name "IIC_0_SCL") (class "Default")
      (node (ref "J7") (pin "10") (pinfunction "10_10") (pintype "passive"))
      (node (ref "R11") (pin "P$2") (pinfunction "2_P$2") (pintype "passive"))
      (node (ref "U4") (pin "1") (pinfunction "P4_0_1") (pintype "bidirectional"))
    )
    (net (code "25") (name "IIC_0_SDA") (class "Default")
      (node (ref "J7") (pin "9") (pinfunction "9_9") (pintype "passive"))
      (node (ref "R14") (pin "P$2") (pinfunction "2_P$2") (pintype "passive"))
      (node (ref "U4") (pin "2") (pinfunction "P4_1_2") (pintype "bidirectional"))
    )
    (net (code "26") (name "IIC_1_SCL") (class "Default")
      (node (ref "J10") (pin "P$5") (pinfunction "P$5_P$5") (pintype "bidirectional"))
      (node (ref "R20") (pin "P$2") (pinfunction "2_P$2") (pintype "passive"))
      (node (ref "U4") (pin "132") (pinfunction "P1_0_132") (pintype "bidirectional"))
    )
    (net (code "27") (name "IIC_1_SDA") (class "Default")
      (node (ref "J10") (pin "P$6") (pinfunction "P$6_P$6") (pintype "bidirectional"))
      (node (ref "R21") (pin "P$2") (pinfunction "2_P$2") (pintype "passive"))
      (node (ref "U4") (pin "131") (pinfunction "P1_1_131") (pintype "bidirectional"))
    )
    (net (code "28") (name "INT_AI_LS_0") (class "Default")
      (node (ref "J15") (pin "P$1") (pinfunction "P$1_P$1") (pintype "bidirectional"))
      (node (ref "U4") (pin "3") (pinfunction "P4_2_3") (pintype "bidirectional"))
    )
    (net (code "29") (name "INT_AI_LS_1") (class "Default")
      (node (ref "J15") (pin "P$2") (pinfunction "P$2_P$2") (pintype "bidirectional"))
      (node (ref "U4") (pin "43") (pinfunction "P4_8_43") (pintype "bidirectional"))
    )
    (net (code "30") (name "INT_AI_LS_2") (class "Default")
      (node (ref "J15") (pin "P$3") (pinfunction "P$3_P$3") (pintype "bidirectional"))
      (node (ref "U4") (pin "53") (pinfunction "P2_3_53") (pintype "bidirectional"))
    )
    (net (code "31") (name "INT_AI_LS_3") (class "Default")
      (node (ref "J15") (pin "P$4") (pinfunction "P$4_P$4") (pintype "bidirectional"))
      (node (ref "U4") (pin "54") (pinfunction "P2_2_54") (pintype "bidirectional"))
    )
    (net (code "32") (name "INT_MI_01") (class "Default")
      (node (ref "J10") (pin "P$39") (pinfunction "P$39_P$39") (pintype "bidirectional"))
      (node (ref "U4") (pin "87") (pinfunction "P3_1_87") (pintype "bidirectional"))
    )
    (net (code "33") (name "INT_MI_02") (class "Default")
      (node (ref "J10") (pin "P$40") (pinfunction "P$40_P$40") (pintype "bidirectional"))
      (node (ref "U4") (pin "86") (pinfunction "P3_2_86") (pintype "bidirectional"))
    )
    (net (code "34") (name "INT_MI_03") (class "Default")
      (node (ref "J10") (pin "P$9") (pinfunction "P$9_P$9") (pintype "bidirectional"))
      (node (ref "U4") (pin "128") (pinfunction "P1_4_128") (pintype "bidirectional"))
    )
    (net (code "35") (name "INT_MI_04") (class "Default")
      (node (ref "J10") (pin "P$10") (pinfunction "P$10_P$10") (pintype "bidirectional"))
      (node (ref "U4") (pin "127") (pinfunction "P1_5_127") (pintype "bidirectional"))
    )
    (net (code "36") (name "INT_MI_05") (class "Default")
      (node (ref "J10") (pin "P$1") (pinfunction "P$1_P$1") (pintype "bidirectional"))
    )
    (net (code "37") (name "LED1{slash}SPEED") (class "Default")
      (node (ref "J4") (pin "11") (pinfunction "YLO_11") (pintype "bidirectional"))
      (node (ref "U3") (pin "23") (pinfunction "LED0/ANEN_SPEED_23") (pintype "bidirectional"))
    )
    (net (code "38") (name "M0_DIR") (class "Default")
      (node (ref "RXS4") (pin "P$1") (pinfunction "1_P$1") (pintype "passive"))
      (node (ref "U4") (pin "39") (pinfunction "P4_12_39") (pintype "bidirectional"))
    )
    (net (code "39") (name "M0_STEP") (class "Default")
      (node (ref "RXS2") (pin "P$1") (pinfunction "1_P$1") (pintype "passive"))
      (node (ref "U4") (pin "16") (pinfunction "PB_0_16") (pintype "bidirectional"))
    )
    (net (code "40") (name "M1_DIR") (class "Default")
      (node (ref "RYS7") (pin "P$1") (pinfunction "1_P$1") (pintype "passive"))
      (node (ref "U4") (pin "40") (pinfunction "P4_11_40") (pintype "bidirectional"))
    )
    (net (code "41") (name "M1_STEP") (class "Default")
      (node (ref "RYS3") (pin "P$1") (pinfunction "1_P$1") (pintype "passive"))
      (node (ref "U4") (pin "36") (pinfunction "P4_15_36") (pintype "bidirectional"))
    )
    (net (code "42") (name "M2_DIR") (class "Default")
      (node (ref "RZS4") (pin "P$1") (pinfunction "1_P$1") (pintype "passive"))
      (node (ref "U4") (pin "41") (pinfunction "P4_10_41") (pintype "bidirectional"))
    )
    (net (code "43") (name "M2_STEP") (class "Default")
      (node (ref "RZS2") (pin "P$1") (pinfunction "1_P$1") (pintype "passive"))
      (node (ref "U4") (pin "37") (pinfunction "P4_14_37") (pintype "bidirectional"))
    )
    (net (code "44") (name "M3_DIR") (class "Default")
      (node (ref "RYS8") (pin "P$1") (pinfunction "1_P$1") (pintype "passive"))
      (node (ref "U4") (pin "42") (pinfunction "P4_9_42") (pintype "bidirectional"))
    )
    (net (code "45") (name "M3_STEP") (class "Default")
      (node (ref "RYS4") (pin "P$1") (pinfunction "1_P$1") (pintype "passive"))
      (node (ref "U4") (pin "38") (pinfunction "P4_13_38") (pintype "bidirectional"))
    )
    (net (code "46") (name "NC") (class "Default")
      (node (ref "J4") (pin "7") (pinfunction "P7_7") (pintype "bidirectional"))
    )
    (net (code "47") (name "Net-(C16-1)") (class "Default")
      (node (ref "C16") (pin "P$1") (pinfunction "1_P$1") (pintype "passive"))
      (node (ref "J2") (pin "P$1") (pinfunction "VBUS_P$1") (pintype "bidirectional"))
      (node (ref "R4") (pin "P$2") (pinfunction "2_P$2") (pintype "passive"))
      (node (ref "R7") (pin "P$2") (pinfunction "2_P$2") (pintype "passive"))
    )
    (net (code "48") (name "Net-(C31-1)") (class "Default")
      (node (ref "C31") (pin "P$1") (pinfunction "1_P$1") (pintype "passive"))
      (node (ref "U4") (pin "62") (pinfunction "VCL1_62") (pintype "bidirectional"))
    )
    (net (code "49") (name "Net-(C37-2)") (class "Default")
      (node (ref "C37") (pin "P$2") (pinfunction "2_P$2") (pintype "passive"))
      (node (ref "U4") (pin "148") (pinfunction "VCL2_148") (pintype "bidirectional"))
    )
    (net (code "50") (name "Net-(C38-1)") (class "Default")
      (node (ref "C38") (pin "P$1") (pinfunction "1_P$1") (pintype "passive"))
      (node (ref "U4") (pin "19") (pinfunction "VCLO_19") (pintype "bidirectional"))
    )
    (net (code "51") (name "Net-(C44-1)") (class "Default")
      (node (ref "C43") (pin "1") (pinfunction "1_1") (pintype "passive"))
      (node (ref "C44") (pin "P$1") (pinfunction "1_P$1") (pintype "passive"))
      (node (ref "FB2/2") (pin "2") (pinfunction "P$2_2") (pintype "bidirectional"))
      (node (ref "U3") (pin "2") (pinfunction "VDDA_3.3_2") (pintype "power_in"))
    )
    (net (code "52") (name "Net-(J2-D+)") (class "Default")
      (node (ref "J2") (pin "P$3") (pinfunction "D+_P$3") (pintype "bidirectional"))
      (node (ref "R6") (pin "P$2") (pinfunction "2_P$2") (pintype "passive"))
    )
    (net (code "53") (name "Net-(J2-D-)") (class "Default")
      (node (ref "J2") (pin "P$2") (pinfunction "D-_P$2") (pintype "bidirectional"))
      (node (ref "R5") (pin "P$2") (pinfunction "2_P$2") (pintype "passive"))
    )
    (net (code "54") (name "Net-(R13-1)") (class "Default")
      (node (ref "LED3") (pin "A") (pinfunction "A_A") (pintype "passive"))
      (node (ref "R13") (pin "P$1") (pinfunction "1_P$1") (pintype "passive"))
    )
    (net (code "55") (name "Net-(R16-2)") (class "Default")
      (node (ref "R16") (pin "P$2") (pinfunction "2_P$2") (pintype "passive"))
      (node (ref "U4") (pin "65") (pinfunction "VLO2(DCDC)_65") (pintype "bidirectional"))
    )
    (net (code "56") (name "Net-(R17-2)") (class "Default")
      (node (ref "R17") (pin "P$2") (pinfunction "2_P$2") (pintype "passive"))
      (node (ref "U4") (pin "64") (pinfunction "VLO1(DCDC)_64") (pintype "bidirectional"))
    )
    (net (code "57") (name "Net-(R19-2)") (class "Default")
      (node (ref "R19") (pin "P$2") (pinfunction "2_P$2") (pintype "passive"))
      (node (ref "U4") (pin "27") (pinfunction "USBHS_RREF_27") (pintype "bidirectional"))
    )
    (net (code "58") (name "Net-(RXS2-2)") (class "Default")
      (node (ref "RXS2") (pin "P$2") (pinfunction "2_P$2") (pintype "passive"))
      (node (ref "U$5") (pin "P$1") (pinfunction "1_P$1") (pintype "passive"))
      (node (ref "U8") (pin "1") (pinfunction "B(2)_1") (pintype "input"))
    )
    (net (code "59") (name "Net-(RXS3-2)") (class "Default")
      (node (ref "RXS3") (pin "P$2") (pinfunction "2_P$2") (pintype "passive"))
      (node (ref "U$12") (pin "P$1") (pinfunction "1_P$1") (pintype "passive"))
      (node (ref "U13") (pin "1") (pinfunction "B(2)_1") (pintype "input"))
    )
    (net (code "60") (name "Net-(RXS4-2)") (class "Default")
      (node (ref "RXS4") (pin "P$2") (pinfunction "2_P$2") (pintype "passive"))
      (node (ref "U$16") (pin "P$1") (pinfunction "1_P$1") (pintype "passive"))
      (node (ref "U17") (pin "1") (pinfunction "B(2)_1") (pintype "input"))
    )
    (net (code "61") (name "Net-(RXS8-2)") (class "Default")
      (node (ref "RXS8") (pin "P$2") (pinfunction "2_P$2") (pintype "passive"))
      (node (ref "U$33") (pin "P$1") (pinfunction "1_P$1") (pintype "passive"))
      (node (ref "U33") (pin "1") (pinfunction "B(2)_1") (pintype "input"))
    )
    (net (code "62") (name "Net-(RYS3-2)") (class "Default")
      (node (ref "RYS3") (pin "P$2") (pinfunction "2_P$2") (pintype "passive"))
      (node (ref "U$6") (pin "P$1") (pinfunction "1_P$1") (pintype "passive"))
      (node (ref "U9") (pin "1") (pinfunction "B(2)_1") (pintype "input"))
    )
    (net (code "63") (name "Net-(RYS4-2)") (class "Default")
      (node (ref "RYS4") (pin "P$2") (pinfunction "2_P$2") (pintype "passive"))
      (node (ref "U$8") (pin "P$1") (pinfunction "1_P$1") (pintype "passive"))
      (node (ref "U10") (pin "1") (pinfunction "B(2)_1") (pintype "input"))
    )
    (net (code "64") (name "Net-(RYS5-2)") (class "Default")
      (node (ref "RYS5") (pin "P$2") (pinfunction "2_P$2") (pintype "passive"))
      (node (ref "U$13") (pin "P$1") (pinfunction "1_P$1") (pintype "passive"))
      (node (ref "U14") (pin "1") (pinfunction "B(2)_1") (pintype "input"))
    )
    (net (code "65") (name "Net-(RYS6-2)") (class "Default")
      (node (ref "RYS6") (pin "P$2") (pinfunction "2_P$2") (pintype "passive"))
      (node (ref "U$14") (pin "P$1") (pinfunction "1_P$1") (pintype "passive"))
      (node (ref "U15") (pin "1") (pinfunction "B(2)_1") (pintype "input"))
    )
    (net (code "66") (name "Net-(RYS7-2)") (class "Default")
      (node (ref "RYS7") (pin "P$2") (pinfunction "2_P$2") (pintype "passive"))
      (node (ref "U$17") (pin "P$1") (pinfunction "1_P$1") (pintype "passive"))
      (node (ref "U18") (pin "1") (pinfunction "B(2)_1") (pintype "input"))
    )
    (net (code "67") (name "Net-(RYS8-2)") (class "Default")
      (node (ref "RYS8") (pin "P$2") (pinfunction "2_P$2") (pintype "passive"))
      (node (ref "U$18") (pin "P$1") (pinfunction "1_P$1") (pintype "passive"))
      (node (ref "U19") (pin "1") (pinfunction "B(2)_1") (pintype "input"))
    )
    (net (code "68") (name "Net-(RYS15-2)") (class "Default")
      (node (ref "RYS15") (pin "P$2") (pinfunction "2_P$2") (pintype "passive"))
      (node (ref "U$34") (pin "P$1") (pinfunction "1_P$1") (pintype "passive"))
      (node (ref "U34") (pin "1") (pinfunction "B(2)_1") (pintype "input"))
    )
    (net (code "69") (name "Net-(RYS16-2)") (class "Default")
      (node (ref "RYS16") (pin "P$2") (pinfunction "2_P$2") (pintype "passive"))
      (node (ref "U$35") (pin "P$1") (pinfunction "1_P$1") (pintype "passive"))
      (node (ref "U35") (pin "1") (pinfunction "B(2)_1") (pintype "input"))
    )
    (net (code "70") (name "Net-(RZS2-2)") (class "Default")
      (node (ref "RZS2") (pin "P$2") (pinfunction "2_P$2") (pintype "passive"))
      (node (ref "U$1") (pin "P$1") (pinfunction "1_P$1") (pintype "passive"))
      (node (ref "U7") (pin "1") (pinfunction "B(2)_1") (pintype "input"))
    )
    (net (code "71") (name "Net-(RZS3-2)") (class "Default")
      (node (ref "RZS3") (pin "P$2") (pinfunction "2_P$2") (pintype "passive"))
      (node (ref "U$10") (pin "P$1") (pinfunction "1_P$1") (pintype "passive"))
      (node (ref "U12") (pin "1") (pinfunction "B(2)_1") (pintype "input"))
    )
    (net (code "72") (name "Net-(RZS4-2)") (class "Default")
      (node (ref "RZS4") (pin "P$2") (pinfunction "2_P$2") (pintype "passive"))
      (node (ref "U$15") (pin "P$1") (pinfunction "1_P$1") (pintype "passive"))
      (node (ref "U16") (pin "1") (pinfunction "B(2)_1") (pintype "input"))
    )
    (net (code "73") (name "Net-(RZS8-2)") (class "Default")
      (node (ref "RZS8") (pin "P$2") (pinfunction "2_P$2") (pintype "passive"))
      (node (ref "U$32") (pin "P$1") (pinfunction "1_P$1") (pintype "passive"))
      (node (ref "U32") (pin "1") (pinfunction "B(2)_1") (pintype "input"))
    )
    (net (code "74") (name "P0_00") (class "Default")
      (node (ref "J7") (pin "3") (pinfunction "3_3") (pintype "passive"))
      (node (ref "U4") (pin "169") (pinfunction "P0_0/AN0\\00_169") (pintype "bidirectional"))
    )
    (net (code "75") (name "P0_01") (class "Default")
      (node (ref "J7") (pin "4") (pinfunction "4_4") (pintype "passive"))
      (node (ref "U4") (pin "168") (pinfunction "P0_1/AN001_168") (pintype "bidirectional"))
    )
    (net (code "76") (name "P0_02") (class "Default")
      (node (ref "J7") (pin "1") (pinfunction "1_1") (pintype "passive"))
      (node (ref "U4") (pin "167") (pinfunction "P0_2/AN002_167") (pintype "bidirectional"))
    )
    (net (code "77") (name "P0_03") (class "Default")
      (node (ref "J7") (pin "2") (pinfunction "2_2") (pintype "passive"))
      (node (ref "U4") (pin "166") (pinfunction "P0_3/PGAVSS000_166") (pintype "bidirectional"))
    )
    (net (code "78") (name "P0_04") (class "Default")
      (node (ref "J8") (pin "9") (pinfunction "9_9") (pintype "passive"))
      (node (ref "U4") (pin "165") (pinfunction "P0_4/AN100_165") (pintype "bidirectional"))
    )
    (net (code "79") (name "P0_05") (class "Default")
      (node (ref "J8") (pin "10") (pinfunction "10_10") (pintype "passive"))
      (node (ref "U4") (pin "164") (pinfunction "P0_5/AN101_164") (pintype "bidirectional"))
    )
    (net (code "80") (name "P0_06") (class "Default")
      (node (ref "J8") (pin "7") (pinfunction "7_7") (pintype "passive"))
      (node (ref "U4") (pin "163") (pinfunction "P0_6/AN102_163") (pintype "bidirectional"))
    )
    (net (code "81") (name "P0_07") (class "Default")
      (node (ref "J8") (pin "8") (pinfunction "8_8") (pintype "passive"))
      (node (ref "U4") (pin "162") (pinfunction "P0_7/PGVSS100_162") (pintype "bidirectional"))
    )
    (net (code "82") (name "P0_08") (class "Default")
      (node (ref "J8") (pin "5") (pinfunction "5_5") (pintype "passive"))
      (node (ref "U4") (pin "161") (pinfunction "P0_8/AN003_161") (pintype "bidirectional"))
    )
    (net (code "83") (name "P0_09") (class "Default")
      (node (ref "J8") (pin "6") (pinfunction "6_6") (pintype "passive"))
      (node (ref "U4") (pin "160") (pinfunction "P0_9/AN004_160") (pintype "bidirectional"))
    )
    (net (code "84") (name "P0_14") (class "Default")
      (node (ref "J8") (pin "3") (pinfunction "3_3") (pintype "passive"))
      (node (ref "U4") (pin "152") (pinfunction "P0_14/DA0/AN005/AN105_152") (pintype "bidirectional"))
    )
    (net (code "85") (name "P0_15") (class "Default")
      (node (ref "J8") (pin "4") (pinfunction "4_4") (pintype "passive"))
      (node (ref "U4") (pin "151") (pinfunction "P0_15/DA1/AN006/AN106_151") (pintype "bidirectional"))
    )
    (net (code "86") (name "P1_02") (class "Default")
      (node (ref "J10") (pin "P$7") (pinfunction "P$7_P$7") (pintype "bidirectional"))
      (node (ref "U4") (pin "130") (pinfunction "P1_2_130") (pintype "bidirectional"))
    )
    (net (code "87") (name "P1_03") (class "Default")
      (node (ref "J10") (pin "P$8") (pinfunction "P$8_P$8") (pintype "bidirectional"))
      (node (ref "U4") (pin "129") (pinfunction "P1_3_129") (pintype "bidirectional"))
    )
    (net (code "88") (name "P1_06") (class "Default")
      (node (ref "J10") (pin "P$11") (pinfunction "P$11_P$11") (pintype "bidirectional"))
      (node (ref "U4") (pin "126") (pinfunction "P1_6_126") (pintype "bidirectional"))
    )
    (net (code "89") (name "P1_07") (class "Default")
      (node (ref "J10") (pin "P$12") (pinfunction "P$12_P$12") (pintype "bidirectional"))
      (node (ref "U4") (pin "125") (pinfunction "P1_7_125") (pintype "bidirectional"))
    )
    (net (code "90") (name "P1_11") (class "Default")
      (node (ref "J10") (pin "P$38") (pinfunction "P$38_P$38") (pintype "bidirectional"))
      (node (ref "U4") (pin "92") (pinfunction "P1_11_92") (pintype "bidirectional"))
    )
    (net (code "91") (name "P1_12") (class "Default")
      (node (ref "J10") (pin "P$37") (pinfunction "P$37_P$37") (pintype "bidirectional"))
      (node (ref "U4") (pin "93") (pinfunction "P1_12_93") (pintype "bidirectional"))
    )
    (net (code "92") (name "P1_13") (class "Default")
      (node (ref "J10") (pin "P$36") (pinfunction "P$36_P$36") (pintype "bidirectional"))
      (node (ref "U4") (pin "94") (pinfunction "P1_13_94") (pintype "bidirectional"))
    )
    (net (code "93") (name "P1_14") (class "Default")
      (node (ref "J10") (pin "P$35") (pinfunction "P$35_P$35") (pintype "bidirectional"))
      (node (ref "U4") (pin "95") (pinfunction "P1_14_95") (pintype "bidirectional"))
    )
    (net (code "94") (name "P1_15") (class "Default")
      (node (ref "J10") (pin "P$34") (pinfunction "P$34_P$34") (pintype "bidirectional"))
      (node (ref "U4") (pin "96") (pinfunction "P1_15_96") (pintype "bidirectional"))
    )
    (net (code "95") (name "P2_00") (class "Default")
      (node (ref "J16") (pin "3") (pinfunction "3_3") (pintype "passive"))
      (node (ref "R3") (pin "P$2") (pinfunction "2_P$2") (pintype "passive"))
      (node (ref "U4") (pin "69") (pinfunction "P2_0(INPUT_ONLY)_69") (pintype "bidirectional"))
    )
    (net (code "96") (name "P2_01") (class "Default")
      (node (ref "J16") (pin "1") (pinfunction "1_1") (pintype "passive"))
      (node (ref "R2") (pin "P$2") (pinfunction "2_P$2") (pintype "passive"))
      (node (ref "U4") (pin "68") (pinfunction "P2_1/MD_68") (pintype "bidirectional"))
    )
    (net (code "97") (name "P3_03") (class "Default")
      (node (ref "J12") (pin "1") (pinfunction "1_1") (pintype "passive"))
      (node (ref "U4") (pin "85") (pinfunction "P3_3_85") (pintype "bidirectional"))
    )
    (net (code "98") (name "P3_04") (class "Default")
      (node (ref "J12") (pin "2") (pinfunction "2_2") (pintype "passive"))
      (node (ref "U4") (pin "82") (pinfunction "P3_4_82") (pintype "bidirectional"))
    )
    (net (code "99") (name "P3_05") (class "Default")
      (node (ref "J12") (pin "3") (pinfunction "3_3") (pintype "passive"))
      (node (ref "U4") (pin "81") (pinfunction "P3_5_81") (pintype "bidirectional"))
    )
    (net (code "100") (name "P3_06") (class "Default")
      (node (ref "J12") (pin "4") (pinfunction "4_4") (pintype "passive"))
      (node (ref "U4") (pin "80") (pinfunction "P3_6_80") (pintype "bidirectional"))
    )
    (net (code "101") (name "P3_07") (class "Default")
      (node (ref "J12") (pin "5") (pinfunction "5_5") (pintype "passive"))
      (node (ref "U4") (pin "79") (pinfunction "P3_7_79") (pintype "bidirectional"))
    )
    (net (code "102") (name "P3_09") (class "Default")
      (node (ref "J12") (pin "6") (pinfunction "6_6") (pintype "passive"))
      (node (ref "U4") (pin "77") (pinfunction "P3_9_77") (pintype "bidirectional"))
    )
    (net (code "103") (name "P3_10") (class "Default")
      (node (ref "J12") (pin "7") (pinfunction "7_7") (pintype "passive"))
      (node (ref "U4") (pin "76") (pinfunction "P3_10_76") (pintype "bidirectional"))
    )
    (net (code "104") (name "P3_11") (class "Default")
      (node (ref "J12") (pin "8") (pinfunction "8_8") (pintype "passive"))
      (node (ref "U4") (pin "75") (pinfunction "P3_11_75") (pintype "bidirectional"))
    )
    (net (code "105") (name "P3_12") (class "Default")
      (node (ref "J12") (pin "9") (pinfunction "9_9") (pintype "passive"))
      (node (ref "U4") (pin "74") (pinfunction "P3_12_74") (pintype "bidirectional"))
    )
    (net (code "106") (name "P5_11") (class "Default")
      (node (ref "J7") (pin "7") (pinfunction "7_7") (pintype "passive"))
      (node (ref "U4") (pin "176") (pinfunction "P5_11_176") (pintype "bidirectional"))
    )
    (net (code "107") (name "P5_12") (class "Default")
      (node (ref "J7") (pin "8") (pinfunction "8_8") (pintype "passive"))
      (node (ref "U4") (pin "175") (pinfunction "P5_12_175") (pintype "bidirectional"))
    )
    (net (code "108") (name "P5_13") (class "Default")
      (node (ref "J7") (pin "5") (pinfunction "5_5") (pintype "passive"))
      (node (ref "U4") (pin "174") (pinfunction "P5_13_174") (pintype "bidirectional"))
    )
    (net (code "109") (name "P6_00") (class "Default")
      (node (ref "J10") (pin "P$13") (pinfunction "P$13_P$13") (pintype "bidirectional"))
      (node (ref "U4") (pin "122") (pinfunction "P6_0_122") (pintype "bidirectional"))
    )
    (net (code "110") (name "P6_01") (class "Default")
      (node (ref "J10") (pin "P$14") (pinfunction "P$14_P$14") (pintype "bidirectional"))
      (node (ref "U4") (pin "121") (pinfunction "P6_1_121") (pintype "bidirectional"))
    )
    (net (code "111") (name "P6_02") (class "Default")
      (node (ref "J10") (pin "P$15") (pinfunction "P$15_P$15") (pintype "bidirectional"))
      (node (ref "U4") (pin "120") (pinfunction "P6_2_120") (pintype "bidirectional"))
    )
    (net (code "112") (name "P6_03") (class "Default")
      (node (ref "J10") (pin "P$16") (pinfunction "P$16_P$16") (pintype "bidirectional"))
      (node (ref "U4") (pin "119") (pinfunction "P6_3_119") (pintype "bidirectional"))
    )
    (net (code "113") (name "P6_04") (class "Default")
      (node (ref "J10") (pin "P$17") (pinfunction "P$17_P$17") (pintype "bidirectional"))
      (node (ref "U4") (pin "118") (pinfunction "P6_4_118") (pintype "bidirectional"))
    )
    (net (code "114") (name "P6_05") (class "Default")
      (node (ref "J10") (pin "P$18") (pinfunction "P$18_P$18") (pintype "bidirectional"))
      (node (ref "U4") (pin "117") (pinfunction "P6_5_117") (pintype "bidirectional"))
    )
    (net (code "115") (name "P6_06") (class "Default")
      (node (ref "J10") (pin "P$19") (pinfunction "P$19_P$19") (pintype "bidirectional"))
      (node (ref "U4") (pin "116") (pinfunction "P6_6_116") (pintype "bidirectional"))
    )
    (net (code "116") (name "P6_07") (class "Default")
      (node (ref "J10") (pin "P$20") (pinfunction "P$20_P$20") (pintype "bidirectional"))
      (node (ref "U4") (pin "115") (pinfunction "P6_7_115") (pintype "bidirectional"))
    )
    (net (code "117") (name "P6_08") (class "Default")
      (node (ref "J10") (pin "P$33") (pinfunction "P$33_P$33") (pintype "bidirectional"))
      (node (ref "U4") (pin "99") (pinfunction "P6_8_99") (pintype "bidirectional"))
    )
    (net (code "118") (name "P6_09") (class "Default")
      (node (ref "J10") (pin "P$32") (pinfunction "P$32_P$32") (pintype "bidirectional"))
      (node (ref "U4") (pin "100") (pinfunction "P6_9_100") (pintype "bidirectional"))
    )
    (net (code "119") (name "P6_10") (class "Default")
      (node (ref "J10") (pin "P$31") (pinfunction "P$31_P$31") (pintype "bidirectional"))
      (node (ref "U4") (pin "101") (pinfunction "P6_10_101") (pintype "bidirectional"))
    )
    (net (code "120") (name "P6_11") (class "Default")
      (node (ref "J10") (pin "P$30") (pinfunction "P$30_P$30") (pintype "bidirectional"))
      (node (ref "U4") (pin "102") (pinfunction "P6_11_102") (pintype "bidirectional"))
    )
    (net (code "121") (name "P6_12") (class "Default")
      (node (ref "J10") (pin "P$29") (pinfunction "P$29_P$29") (pintype "bidirectional"))
      (node (ref "U4") (pin "103") (pinfunction "P6_12_103") (pintype "bidirectional"))
    )
    (net (code "122") (name "P6_13") (class "Default")
      (node (ref "J10") (pin "P$28") (pinfunction "P$28_P$28") (pintype "bidirectional"))
      (node (ref "U4") (pin "104") (pinfunction "P6_13_104") (pintype "bidirectional"))
    )
    (net (code "123") (name "P6_14") (class "Default")
      (node (ref "J10") (pin "P$27") (pinfunction "P$27_P$27") (pintype "bidirectional"))
      (node (ref "U4") (pin "105") (pinfunction "P6_14_105") (pintype "bidirectional"))
    )
    (net (code "124") (name "P6_15") (class "Default")
      (node (ref "J10") (pin "P$26") (pinfunction "P$26_P$26") (pintype "bidirectional"))
      (node (ref "U4") (pin "106") (pinfunction "P6_15_106") (pintype "bidirectional"))
    )
    (net (code "125") (name "P7_06") (class "Default")
      (node (ref "U4") (pin "14") (pinfunction "P7_6_14") (pintype "bidirectional"))
    )
    (net (code "126") (name "P7_07") (class "Default")
      (node (ref "U4") (pin "15") (pinfunction "P7_7_15") (pintype "bidirectional"))
    )
    (net (code "127") (name "P8_00") (class "Default")
      (node (ref "J10") (pin "P$4") (pinfunction "P$4_P$4") (pintype "bidirectional"))
      (node (ref "U4") (pin "133") (pinfunction "P8_0_133") (pintype "bidirectional"))
    )
    (net (code "128") (name "P8_01") (class "Default")
      (node (ref "J10") (pin "P$3") (pinfunction "P$3_P$3") (pintype "bidirectional"))
      (node (ref "U4") (pin "134") (pinfunction "P8_1_134") (pintype "bidirectional"))
    )
    (net (code "129") (name "P8_02") (class "Default")
      (node (ref "J10") (pin "P$2") (pinfunction "P$2_P$2") (pintype "bidirectional"))
      (node (ref "U4") (pin "135") (pinfunction "P8_2_135") (pintype "bidirectional"))
    )
    (net (code "130") (name "P8_03") (class "Default")
      (node (ref "J8") (pin "2") (pinfunction "2_2") (pintype "passive"))
      (node (ref "U4") (pin "136") (pinfunction "P8_3_136") (pintype "bidirectional"))
    )
    (net (code "131") (name "P8_04") (class "Default")
      (node (ref "J8") (pin "1") (pinfunction "1_1") (pintype "passive"))
      (node (ref "U4") (pin "137") (pinfunction "P8_4_137") (pintype "bidirectional"))
    )
    (net (code "132") (name "P8_05") (class "Default")
      (node (ref "J7") (pin "6") (pinfunction "6_6") (pintype "passive"))
      (node (ref "U4") (pin "173") (pinfunction "P8_5_173") (pintype "bidirectional"))
    )
    (net (code "133") (name "P9_05") (class "Default")
      (node (ref "J12") (pin "10") (pinfunction "10_10") (pintype "passive"))
      (node (ref "U4") (pin "73") (pinfunction "P9_5_73") (pintype "bidirectional"))
    )
    (net (code "134") (name "P9_06") (class "Default")
      (node (ref "J16") (pin "9") (pinfunction "9_9") (pintype "passive"))
      (node (ref "R10") (pin "P$2") (pinfunction "2_P$2") (pintype "passive"))
      (node (ref "U4") (pin "72") (pinfunction "P9_6_72") (pintype "bidirectional"))
    )
    (net (code "135") (name "P9_07") (class "Default")
      (node (ref "J16") (pin "7") (pinfunction "7_7") (pintype "passive"))
      (node (ref "R9") (pin "P$2") (pinfunction "2_P$2") (pintype "passive"))
      (node (ref "U4") (pin "71") (pinfunction "P9_7_71") (pintype "bidirectional"))
    )
    (net (code "136") (name "P9_08") (class "Default")
      (node (ref "J16") (pin "5") (pinfunction "5_5") (pintype "passive"))
      (node (ref "R8") (pin "P$2") (pinfunction "2_P$2") (pintype "passive"))
      (node (ref "U4") (pin "70") (pinfunction "P9_8_70") (pintype "bidirectional"))
    )
    (net (code "137") (name "PA_00") (class "Default")
      (node (ref "J10") (pin "P$21") (pinfunction "P$21_P$21") (pintype "bidirectional"))
      (node (ref "U4") (pin "114") (pinfunction "PA_0_114") (pintype "bidirectional"))
    )
    (net (code "138") (name "PA_01") (class "Default")
      (node (ref "J10") (pin "P$22") (pinfunction "P$22_P$22") (pintype "bidirectional"))
      (node (ref "U4") (pin "113") (pinfunction "PA_1_113") (pintype "bidirectional"))
    )
    (net (code "139") (name "PA_08") (class "Default")
      (node (ref "J10") (pin "P$25") (pinfunction "P$25_P$25") (pintype "bidirectional"))
      (node (ref "U4") (pin "107") (pinfunction "PA_8_107") (pintype "bidirectional"))
    )
    (net (code "140") (name "PA_09") (class "Default")
      (node (ref "J10") (pin "P$24") (pinfunction "P$24_P$24") (pintype "bidirectional"))
      (node (ref "U4") (pin "108") (pinfunction "PA_9_108") (pintype "bidirectional"))
    )
    (net (code "141") (name "PA_10") (class "Default")
      (node (ref "J10") (pin "P$23") (pinfunction "P$23_P$23") (pintype "bidirectional"))
      (node (ref "U4") (pin "109") (pinfunction "PA_10_109") (pintype "bidirectional"))
    )
    (net (code "142") (name "R51") (class "Default")
      (node (ref "J4") (pin "12") (pinfunction "YHI_12") (pintype "bidirectional"))
      (node (ref "R23") (pin "P$1") (pinfunction "1_P$1") (pintype "passive"))
    )
    (net (code "143") (name "R52") (class "Default")
      (node (ref "J4") (pin "9") (pinfunction "GHI_9") (pintype "bidirectional"))
      (node (ref "R24") (pin "P$1") (pinfunction "1_P$1") (pintype "passive"))
    )
    (net (code "144") (name "RELAY_0") (class "Default")
      (node (ref "RYS6") (pin "P$1") (pinfunction "1_P$1") (pintype "passive"))
      (node (ref "U4") (pin "59") (pinfunction "P9_1_59") (pintype "bidirectional"))
    )
    (net (code "145") (name "RELAY_1") (class "Default")
      (node (ref "RZS3") (pin "P$1") (pinfunction "1_P$1") (pintype "passive"))
      (node (ref "U4") (pin "58") (pinfunction "P9_0_58") (pintype "bidirectional"))
    )
    (net (code "146") (name "RELAY_2") (class "Default")
      (node (ref "RYS5") (pin "P$1") (pinfunction "1_P$1") (pintype "passive"))
      (node (ref "U4") (pin "57") (pinfunction "P3_15_57") (pintype "bidirectional"))
    )
    (net (code "147") (name "RELAY_3") (class "Default")
      (node (ref "RXS3") (pin "P$1") (pinfunction "1_P$1") (pintype "passive"))
      (node (ref "U4") (pin "56") (pinfunction "P3_14_56") (pintype "bidirectional"))
    )
    (net (code "148") (name "RELAY_4") (class "Default")
      (node (ref "RYS16") (pin "P$1") (pinfunction "1_P$1") (pintype "passive"))
      (node (ref "U4") (pin "55") (pinfunction "P3_13_55") (pintype "bidirectional"))
    )
    (net (code "149") (name "RELAY_5") (class "Default")
      (node (ref "RZS8") (pin "P$1") (pinfunction "1_P$1") (pintype "passive"))
      (node (ref "U4") (pin "52") (pinfunction "P2_4_52") (pintype "bidirectional"))
    )
    (net (code "150") (name "RELAY_6") (class "Default")
      (node (ref "RYS15") (pin "P$1") (pinfunction "1_P$1") (pintype "passive"))
      (node (ref "U4") (pin "51") (pinfunction "P2_5_51") (pintype "bidirectional"))
    )
    (net (code "151") (name "RELAY_7") (class "Default")
      (node (ref "RXS8") (pin "P$1") (pinfunction "1_P$1") (pintype "passive"))
      (node (ref "U4") (pin "50") (pinfunction "P2_6_50") (pintype "bidirectional"))
    )
    (net (code "152") (name "RESET") (class "Default")
      (node (ref "C57") (pin "P$1") (pinfunction "1_P$1") (pintype "passive"))
      (node (ref "J11") (pin "9") (pinfunction "9_9") (pintype "passive"))
      (node (ref "R18") (pin "P$1") (pinfunction "1_P$1") (pintype "passive"))
      (node (ref "U4") (pin "67") (pinfunction "RES#_67") (pintype "bidirectional"))
    )
    (net (code "153") (name "REXT") (class "Default")
      (node (ref "C47") (pin "P$1") (pinfunction "1_P$1") (pintype "passive"))
      (node (ref "R25") (pin "P$2") (pinfunction "2_P$2") (pintype "passive"))
      (node (ref "U3") (pin "9") (pinfunction "REXT_9") (pintype "input"))
    )
    (net (code "154") (name "RXD0") (class "Default")
      (node (ref "R31") (pin "P$2") (pinfunction "2_P$2") (pintype "passive"))
      (node (ref "U3") (pin "13") (pinfunction "RXD0_13") (pintype "bidirectional"))
    )
    (net (code "155") (name "RXD1") (class "Default")
      (node (ref "R30") (pin "P$2") (pinfunction "2_P$2") (pintype "passive"))
      (node (ref "U3") (pin "12") (pinfunction "RXD1_12") (pintype "bidirectional"))
    )
    (net (code "156") (name "RXER") (class "Default")
      (node (ref "R32") (pin "P$2") (pinfunction "2_P$2") (pintype "passive"))
      (node (ref "U3") (pin "17") (pinfunction "RXER_17") (pintype "bidirectional"))
    )
    (net (code "157") (name "RXM") (class "Default")
      (node (ref "J4") (pin "6") (pinfunction "RD-_6") (pintype "bidirectional"))
      (node (ref "U3") (pin "3") (pinfunction "RXM_3") (pintype "bidirectional"))
    )
    (net (code "158") (name "RXP") (class "Default")
      (node (ref "J4") (pin "3") (pinfunction "RD+_3") (pintype "bidirectional"))
      (node (ref "U3") (pin "4") (pinfunction "RXP_4") (pintype "bidirectional"))
    )
    (net (code "159") (name "SD1_CD") (class "Default")
      (node (ref "J9") (pin "10") (pinfunction "CD_SWITCH2_10") (pintype "bidirectional"))
      (node (ref "U4") (pin "146") (pinfunction "P5_6/AN019_146") (pintype "bidirectional"))
    )
    (net (code "160") (name "SD1_CLK") (class "Default")
      (node (ref "J9") (pin "5") (pinfunction "CLOCK_5") (pintype "bidirectional"))
      (node (ref "U4") (pin "140") (pinfunction "P5_0/AN016_140") (pintype "bidirectional"))
    )
    (net (code "161") (name "SD1_CMD") (class "Default")
      (node (ref "J9") (pin "3") (pinfunction "COMMAND/RESPONSE_3") (pintype "bidirectional"))
      (node (ref "U4") (pin "141") (pinfunction "P5_1/AN116_141") (pintype "bidirectional"))
    )
    (net (code "162") (name "SD1_DAT0") (class "Default")
      (node (ref "J9") (pin "7") (pinfunction "DATA_LINE[BIT_0]_7") (pintype "bidirectional"))
      (node (ref "U4") (pin "142") (pinfunction "P5_2/AN017_142") (pintype "bidirectional"))
    )
    (net (code "163") (name "SD1_DAT1") (class "Default")
      (node (ref "J9") (pin "8") (pinfunction "DATA_LINE[BIT_1]_8") (pintype "bidirectional"))
      (node (ref "U4") (pin "143") (pinfunction "P5_3/AN117_143") (pintype "bidirectional"))
    )
    (net (code "164") (name "SD1_DAT2") (class "Default")
      (node (ref "J9") (pin "1") (pinfunction "DATA_LINE[BIT_2]_1") (pintype "bidirectional"))
      (node (ref "U4") (pin "144") (pinfunction "P5_4/AN018_144") (pintype "bidirectional"))
    )
    (net (code "165") (name "SD1_DAT3") (class "Default")
      (node (ref "J9") (pin "2") (pinfunction "CARD_DETECT/DATA_LINE[BIT_3]_2") (pintype "bidirectional"))
      (node (ref "U4") (pin "145") (pinfunction "P5_5/AN118_145") (pintype "bidirectional"))
    )
    (net (code "166") (name "SD1_WP") (class "Default")
      (node (ref "J9") (pin "9") (pinfunction "CD_SWITCH1_9") (pintype "bidirectional"))
      (node (ref "U4") (pin "147") (pinfunction "P5_7/AN119_147") (pintype "bidirectional"))
    )
    (net (code "167") (name "TCK") (class "Default")
      (node (ref "J11") (pin "7") (pinfunction "7_7") (pintype "passive"))
      (node (ref "U4") (pin "88") (pinfunction "P3_0_88") (pintype "bidirectional"))
    )
    (net (code "168") (name "TDI") (class "Default")
      (node (ref "J11") (pin "1") (pinfunction "1_1") (pintype "passive"))
      (node (ref "U4") (pin "91") (pinfunction "P1_10_91") (pintype "bidirectional"))
    )
    (net (code "169") (name "TDO") (class "Default")
      (node (ref "J11") (pin "3") (pinfunction "3_3") (pintype "passive"))
      (node (ref "U4") (pin "90") (pinfunction "P1_9_90") (pintype "bidirectional"))
    )
    (net (code "170") (name "TMS") (class "Default")
      (node (ref "J11") (pin "5") (pinfunction "5_5") (pintype "passive"))
      (node (ref "U4") (pin "89") (pinfunction "P1_8_89") (pintype "bidirectional"))
    )
    (net (code "171") (name "TXM") (class "Default")
      (node (ref "J4") (pin "2") (pinfunction "TD-_2") (pintype "bidirectional"))
      (node (ref "U3") (pin "5") (pinfunction "TXM_5") (pintype "bidirectional"))
    )
    (net (code "172") (name "TXP") (class "Default")
      (node (ref "J4") (pin "1") (pinfunction "TD+_1") (pintype "bidirectional"))
      (node (ref "U3") (pin "6") (pinfunction "TXP_6") (pintype "bidirectional"))
    )
    (net (code "173") (name "USBHS_FAULT") (class "Default")
      (node (ref "R12") (pin "P$1") (pinfunction "1_P$1") (pintype "passive"))
      (node (ref "U2") (pin "3") (pinfunction "FLG_3") (pintype "input"))
      (node (ref "U4") (pin "78") (pinfunction "P3_8_78") (pintype "bidirectional"))
    )
    (net (code "174") (name "USBHS_N") (class "Default")
      (node (ref "J3") (pin "D-") (pinfunction "D-_D-") (pintype "bidirectional"))
      (node (ref "U4") (pin "31") (pinfunction "USBHS_DM_31") (pintype "bidirectional"))
    )
    (net (code "175") (name "USBHS_P") (class "Default")
      (node (ref "J3") (pin "D+") (pinfunction "D+_D+") (pintype "bidirectional"))
      (node (ref "U4") (pin "32") (pinfunction "USBHS_DP_32") (pintype "bidirectional"))
    )
    (net (code "176") (name "USBHS_VBUS") (class "Default")
      (node (ref "C11") (pin "P$1") (pinfunction "1_P$1") (pintype "passive"))
      (node (ref "C15") (pin "1") (pinfunction "1_1") (pintype "passive"))
      (node (ref "J3") (pin "VBUS") (pinfunction "VBUS_VBUS") (pintype "power_in"))
      (node (ref "U2") (pin "5") (pinfunction "OUT_5") (pintype "input"))
      (node (ref "U4") (pin "17") (pinfunction "PB_1_17") (pintype "bidirectional"))
    )
    (net (code "177") (name "USBHS_VBUSEN") (class "Default")
      (node (ref "R1") (pin "P$1") (pinfunction "1_P$1") (pintype "passive"))
      (node (ref "U2") (pin "1") (pinfunction "EN_1") (pintype "input"))
    )
    (net (code "178") (name "USB_N") (class "Default")
      (node (ref "R5") (pin "P$1") (pinfunction "1_P$1") (pintype "passive"))
      (node (ref "U4") (pin "46") (pinfunction "USB_DM_46") (pintype "bidirectional"))
    )
    (net (code "179") (name "USB_P") (class "Default")
      (node (ref "R6") (pin "P$1") (pinfunction "1_P$1") (pintype "passive"))
      (node (ref "U4") (pin "47") (pinfunction "USB_DP_47") (pintype "bidirectional"))
    )
    (net (code "180") (name "USB_VBUS_B") (class "Default")
      (node (ref "R4") (pin "P$1") (pinfunction "1_P$1") (pintype "passive"))
      (node (ref "U4") (pin "44") (pinfunction "P4_7_44") (pintype "bidirectional"))
    )
    (net (code "181") (name "VCL_F(FLASH)") (class "Default")
      (node (ref "C36") (pin "P$2") (pinfunction "2_P$2") (pintype "passive"))
      (node (ref "U4") (pin "112") (pinfunction "VCL_F(FLASH)_112") (pintype "bidirectional"))
    )
    (net (code "182") (name "VDD") (class "Default")
      (node (ref "C1") (pin "P$2") (pinfunction "2_P$2") (pintype "passive"))
      (node (ref "C10") (pin "P$2") (pinfunction "2_P$2") (pintype "passive"))
      (node (ref "C13") (pin "P$2") (pinfunction "2_P$2") (pintype "passive"))
      (node (ref "C14") (pin "P$2") (pinfunction "2_P$2") (pintype "passive"))
      (node (ref "C2") (pin "P$2") (pinfunction "2_P$2") (pintype "passive"))
      (node (ref "C30") (pin "P$2") (pinfunction "2_P$2") (pintype "passive"))
      (node (ref "C32") (pin "P$1") (pinfunction "1_P$1") (pintype "passive"))
      (node (ref "C33") (pin "P$1") (pinfunction "1_P$1") (pintype "passive"))
      (node (ref "C34") (pin "P$1") (pinfunction "1_P$1") (pintype "passive"))
      (node (ref "C35") (pin "P$1") (pinfunction "1_P$1") (pintype "passive"))
      (node (ref "C48") (pin "1") (pinfunction "1_1") (pintype "passive"))
      (node (ref "C49") (pin "P$1") (pinfunction "1_P$1") (pintype "passive"))
      (node (ref "C54") (pin "P$2") (pinfunction "2_P$2") (pintype "passive"))
      (node (ref "C55") (pin "P$2") (pinfunction "2_P$2") (pintype "passive"))
      (node (ref "C56") (pin "P$2") (pinfunction "2_P$2") (pintype "passive"))
      (node (ref "C58") (pin "P$1") (pinfunction "1_P$1") (pintype "passive"))
      (node (ref "C59") (pin "P$1") (pinfunction "1_P$1") (pintype "passive"))
      (node (ref "C60") (pin "P$1") (pinfunction "1_P$1") (pintype "passive"))
      (node (ref "C61") (pin "P$2") (pinfunction "2_P$2") (pintype "passive"))
      (node (ref "FB2/2") (pin "1") (pinfunction "P$1_1") (pintype "bidirectional"))
      (node (ref "J11") (pin "2") (pinfunction "2_2") (pintype "passive"))
      (node (ref "J11") (pin "4") (pinfunction "4_4") (pintype "passive"))
      (node (ref "J9") (pin "4") (pinfunction "SUPPLY_VOLTAGE_4") (pintype "power_in"))
      (node (ref "L3") (pin "2") (pinfunction "P$2_2") (pintype "bidirectional"))
      (node (ref "R10") (pin "P$1") (pinfunction "1_P$1") (pintype "passive"))
      (node (ref "R11") (pin "P$1") (pinfunction "1_P$1") (pintype "passive"))
      (node (ref "R13") (pin "P$2") (pinfunction "2_P$2") (pintype "passive"))
      (node (ref "R14") (pin "P$1") (pinfunction "1_P$1") (pintype "passive"))
      (node (ref "R18") (pin "P$2") (pinfunction "2_P$2") (pintype "passive"))
      (node (ref "R2") (pin "P$1") (pinfunction "1_P$1") (pintype "passive"))
      (node (ref "R20") (pin "P$1") (pinfunction "1_P$1") (pintype "passive"))
      (node (ref "R21") (pin "P$1") (pinfunction "1_P$1") (pintype "passive"))
      (node (ref "R23") (pin "P$2") (pinfunction "2_P$2") (pintype "passive"))
      (node (ref "R24") (pin "P$2") (pinfunction "2_P$2") (pintype "passive"))
      (node (ref "R26") (pin "P$2") (pinfunction "2_P$2") (pintype "passive"))
      (node (ref "R27") (pin "P$2") (pinfunction "2_P$2") (pintype "passive"))
      (node (ref "R28") (pin "P$2") (pinfunction "2_P$2") (pintype "passive"))
      (node (ref "R29") (pin "P$2") (pinfunction "2_P$2") (pintype "passive"))
      (node (ref "R3") (pin "P$1") (pinfunction "1_P$1") (pintype "passive"))
      (node (ref "R8") (pin "P$1") (pinfunction "1_P$1") (pintype "passive"))
      (node (ref "R9") (pin "P$1") (pinfunction "1_P$1") (pintype "passive"))
      (node (ref "U3") (pin "14") (pinfunction "VDDIO_14") (pintype "power_in"))
      (node (ref "U4") (pin "110") (pinfunction "VCC(IO)5_110") (pintype "bidirectional"))
      (node (ref "U4") (pin "123") (pinfunction "VCC(IO)6_123") (pintype "bidirectional"))
      (node (ref "U4") (pin "138") (pinfunction "VCC(IO)7_138") (pintype "bidirectional"))
      (node (ref "U4") (pin "149") (pinfunction "VCC(IO)8_149") (pintype "bidirectional"))
      (node (ref "U4") (pin "154") (pinfunction "VREFH_154") (pintype "bidirectional"))
      (node (ref "U4") (pin "155") (pinfunction "AVCC0_155") (pintype "bidirectional"))
      (node (ref "U4") (pin "158") (pinfunction "VREFH0_158") (pintype "bidirectional"))
      (node (ref "U4") (pin "171") (pinfunction "VCC(IO)9_171") (pintype "bidirectional"))
      (node (ref "U4") (pin "25") (pinfunction "VCC1_25") (pintype "bidirectional"))
      (node (ref "U4") (pin "26") (pinfunction "AVCC_SUBHS_26") (pintype "bidirectional"))
      (node (ref "U4") (pin "34") (pinfunction "VCC_USBHS_34") (pintype "bidirectional"))
      (node (ref "U4") (pin "48") (pinfunction "VCC_USB_48") (pintype "bidirectional"))
      (node (ref "U4") (pin "61") (pinfunction "VCC(IO)2_61") (pintype "bidirectional"))
      (node (ref "U4") (pin "84") (pinfunction "VCC(IO)3_84") (pintype "bidirectional"))
      (node (ref "U4") (pin "97") (pinfunction "VCC(IO)4_97") (pintype "bidirectional"))
    )
    (net (code "183") (name "VDD5") (class "Default")
      (node (ref "C5") (pin "P$1") (pinfunction "1_P$1") (pintype "passive"))
      (node (ref "C8") (pin "P$1") (pinfunction "1_P$1") (pintype "passive"))
      (node (ref "J1") (pin "5") (pinfunction "5_5") (pintype "passive"))
      (node (ref "J1") (pin "6") (pinfunction "6_6") (pintype "passive"))
      (node (ref "R1") (pin "P$2") (pinfunction "2_P$2") (pintype "passive"))
      (node (ref "R12") (pin "P$2") (pinfunction "2_P$2") (pintype "passive"))
      (node (ref "U2") (pin "4") (pinfunction "VIN_4") (pintype "input"))
    )
    (net (code "184") (name "VDD12") (class "Default")
      (node (ref "J1") (pin "7") (pinfunction "7_7") (pintype "passive"))
      (node (ref "J1") (pin "8") (pinfunction "8_8") (pintype "passive"))
    )
    (net (code "185") (name "VDDIN") (class "Default")
      (node (ref "J1") (pin "3") (pinfunction "3_3") (pintype "passive"))
      (node (ref "J1") (pin "4") (pinfunction "4_4") (pintype "passive"))
      (node (ref "L3") (pin "1") (pinfunction "P$1_1") (pintype "bidirectional"))
    )
    (net (code "186") (name "VDD_1.2") (class "Default")
      (node (ref "C45") (pin "P$1") (pinfunction "1_P$1") (pintype "passive"))
      (node (ref "C46") (pin "P$1") (pinfunction "1_P$1") (pintype "passive"))
      (node (ref "U3") (pin "1") (pinfunction "VDD_1.2_1") (pintype "power_in"))
    )
    (net (code "187") (name "XCIN") (class "Default")
      (node (ref "C50") (pin "P$1") (pinfunction "1_P$1") (pintype "passive"))
      (node (ref "U4") (pin "20") (pinfunction "XCIN_20") (pintype "bidirectional"))
      (node (ref "X3") (pin "P$1") (pinfunction "P$1_P$1") (pintype "bidirectional"))
    )
    (net (code "188") (name "XCOUT") (class "Default")
      (node (ref "C51") (pin "P$1") (pinfunction "1_P$1") (pintype "passive"))
      (node (ref "U4") (pin "21") (pinfunction "XCOUT_21") (pintype "bidirectional"))
      (node (ref "X3") (pin "P$2") (pinfunction "P$2_P$2") (pintype "bidirectional"))
    )
    (net (code "189") (name "XII") (class "Default")
      (node (ref "C42") (pin "P$1") (pinfunction "1_P$1") (pintype "passive"))
      (node (ref "U$3") (pin "1") (pinfunction "1_1") (pintype "bidirectional"))
      (node (ref "U3") (pin "8") (pinfunction "XI_8") (pintype "input"))
    )
    (net (code "190") (name "XOO") (class "Default")
      (node (ref "C41") (pin "P$1") (pinfunction "1_P$1") (pintype "passive"))
      (node (ref "U$3") (pin "3") (pinfunction "3_3") (pintype "bidirectional"))
      (node (ref "U3") (pin "7") (pinfunction "XO_7") (pintype "output"))
    )
    (net (code "191") (name "XTAL1") (class "Default")
      (node (ref "C52") (pin "P$1") (pinfunction "1_P$1") (pintype "passive"))
      (node (ref "U4") (pin "23") (pinfunction "P2_13/XTAL_23") (pintype "bidirectional"))
      (node (ref "X4") (pin "1") (pinfunction "1_1") (pintype "bidirectional"))
    )
    (net (code "192") (name "XTAL2") (class "Default")
      (node (ref "C53") (pin "P$1") (pinfunction "1_P$1") (pintype "passive"))
      (node (ref "U4") (pin "24") (pinfunction "P2_12/EXTAL_24") (pintype "bidirectional"))
      (node (ref "X4") (pin "3") (pinfunction "3_3") (pintype "bidirectional"))
    )
    (net (code "193") (name "unconnected-(U4-VBAT-Pad18)") (class "Default")
      (node (ref "U4") (pin "18") (pinfunction "VBAT_18") (pintype "bidirectional"))
    )
  )
)
